# ProProject_AstrAlim_2024-04-22.net
KiCad netlist of a schematic drawn in EasyEDA Pro
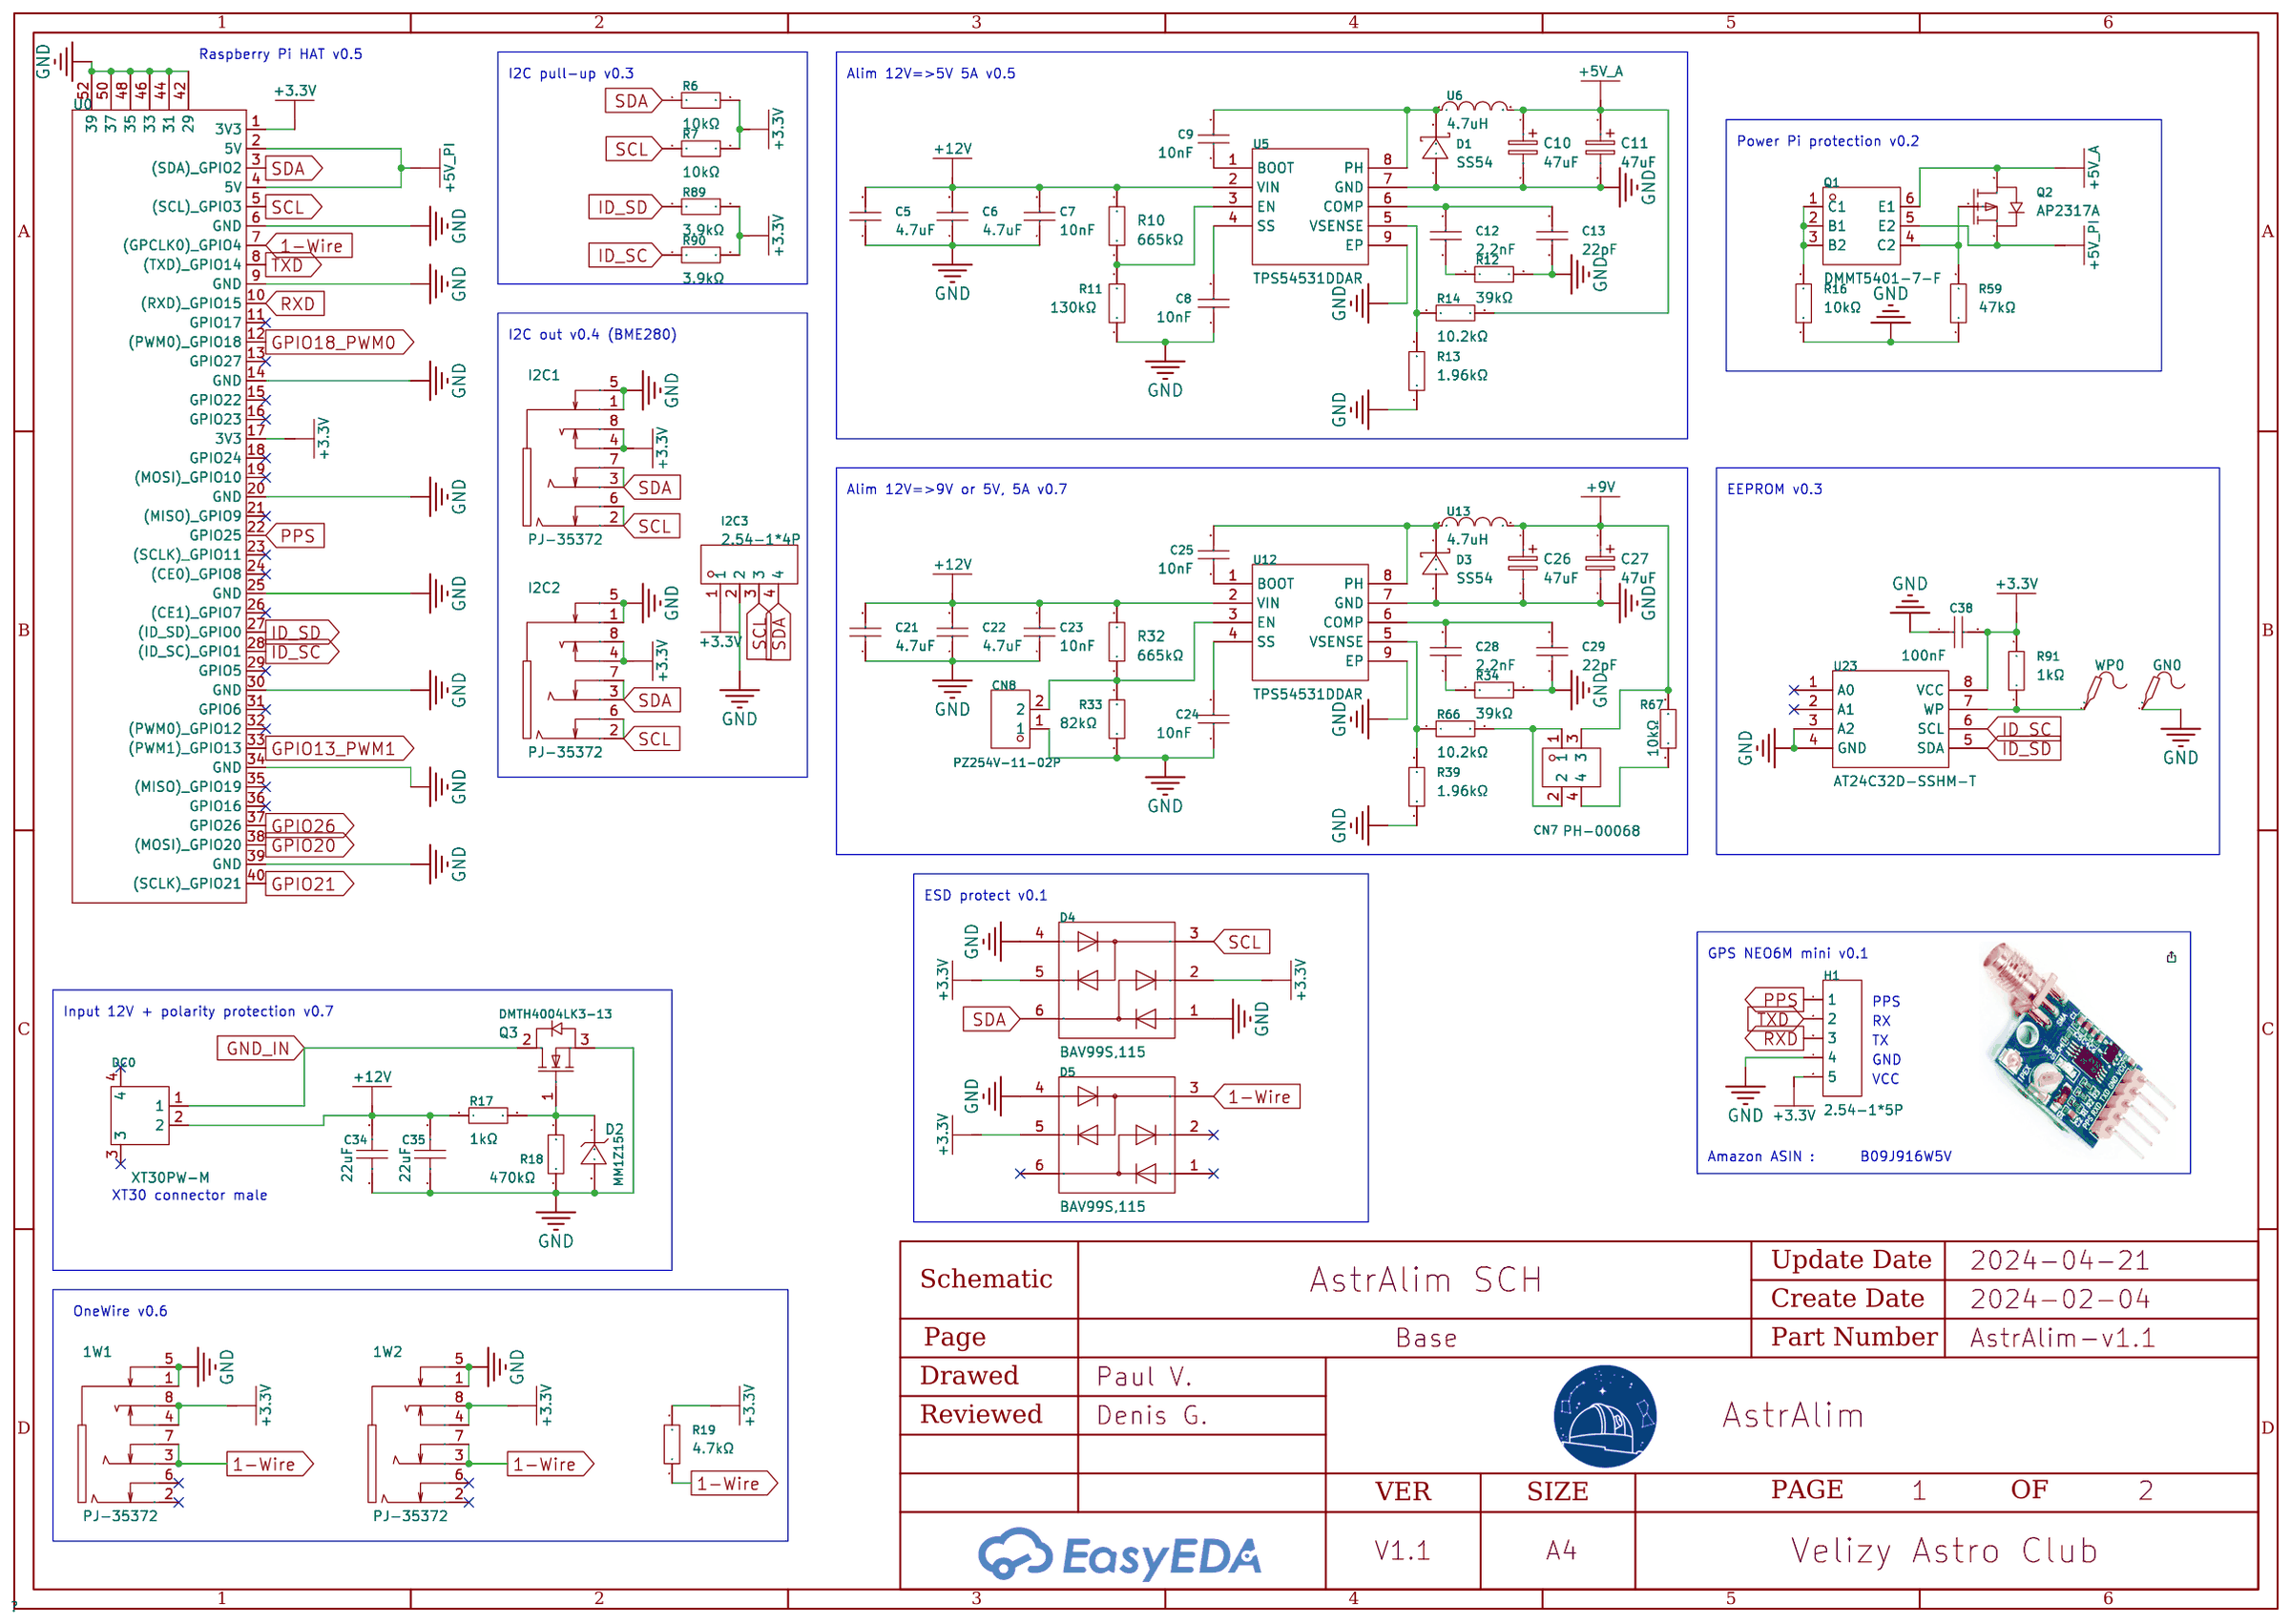
[diagram p0: Base]
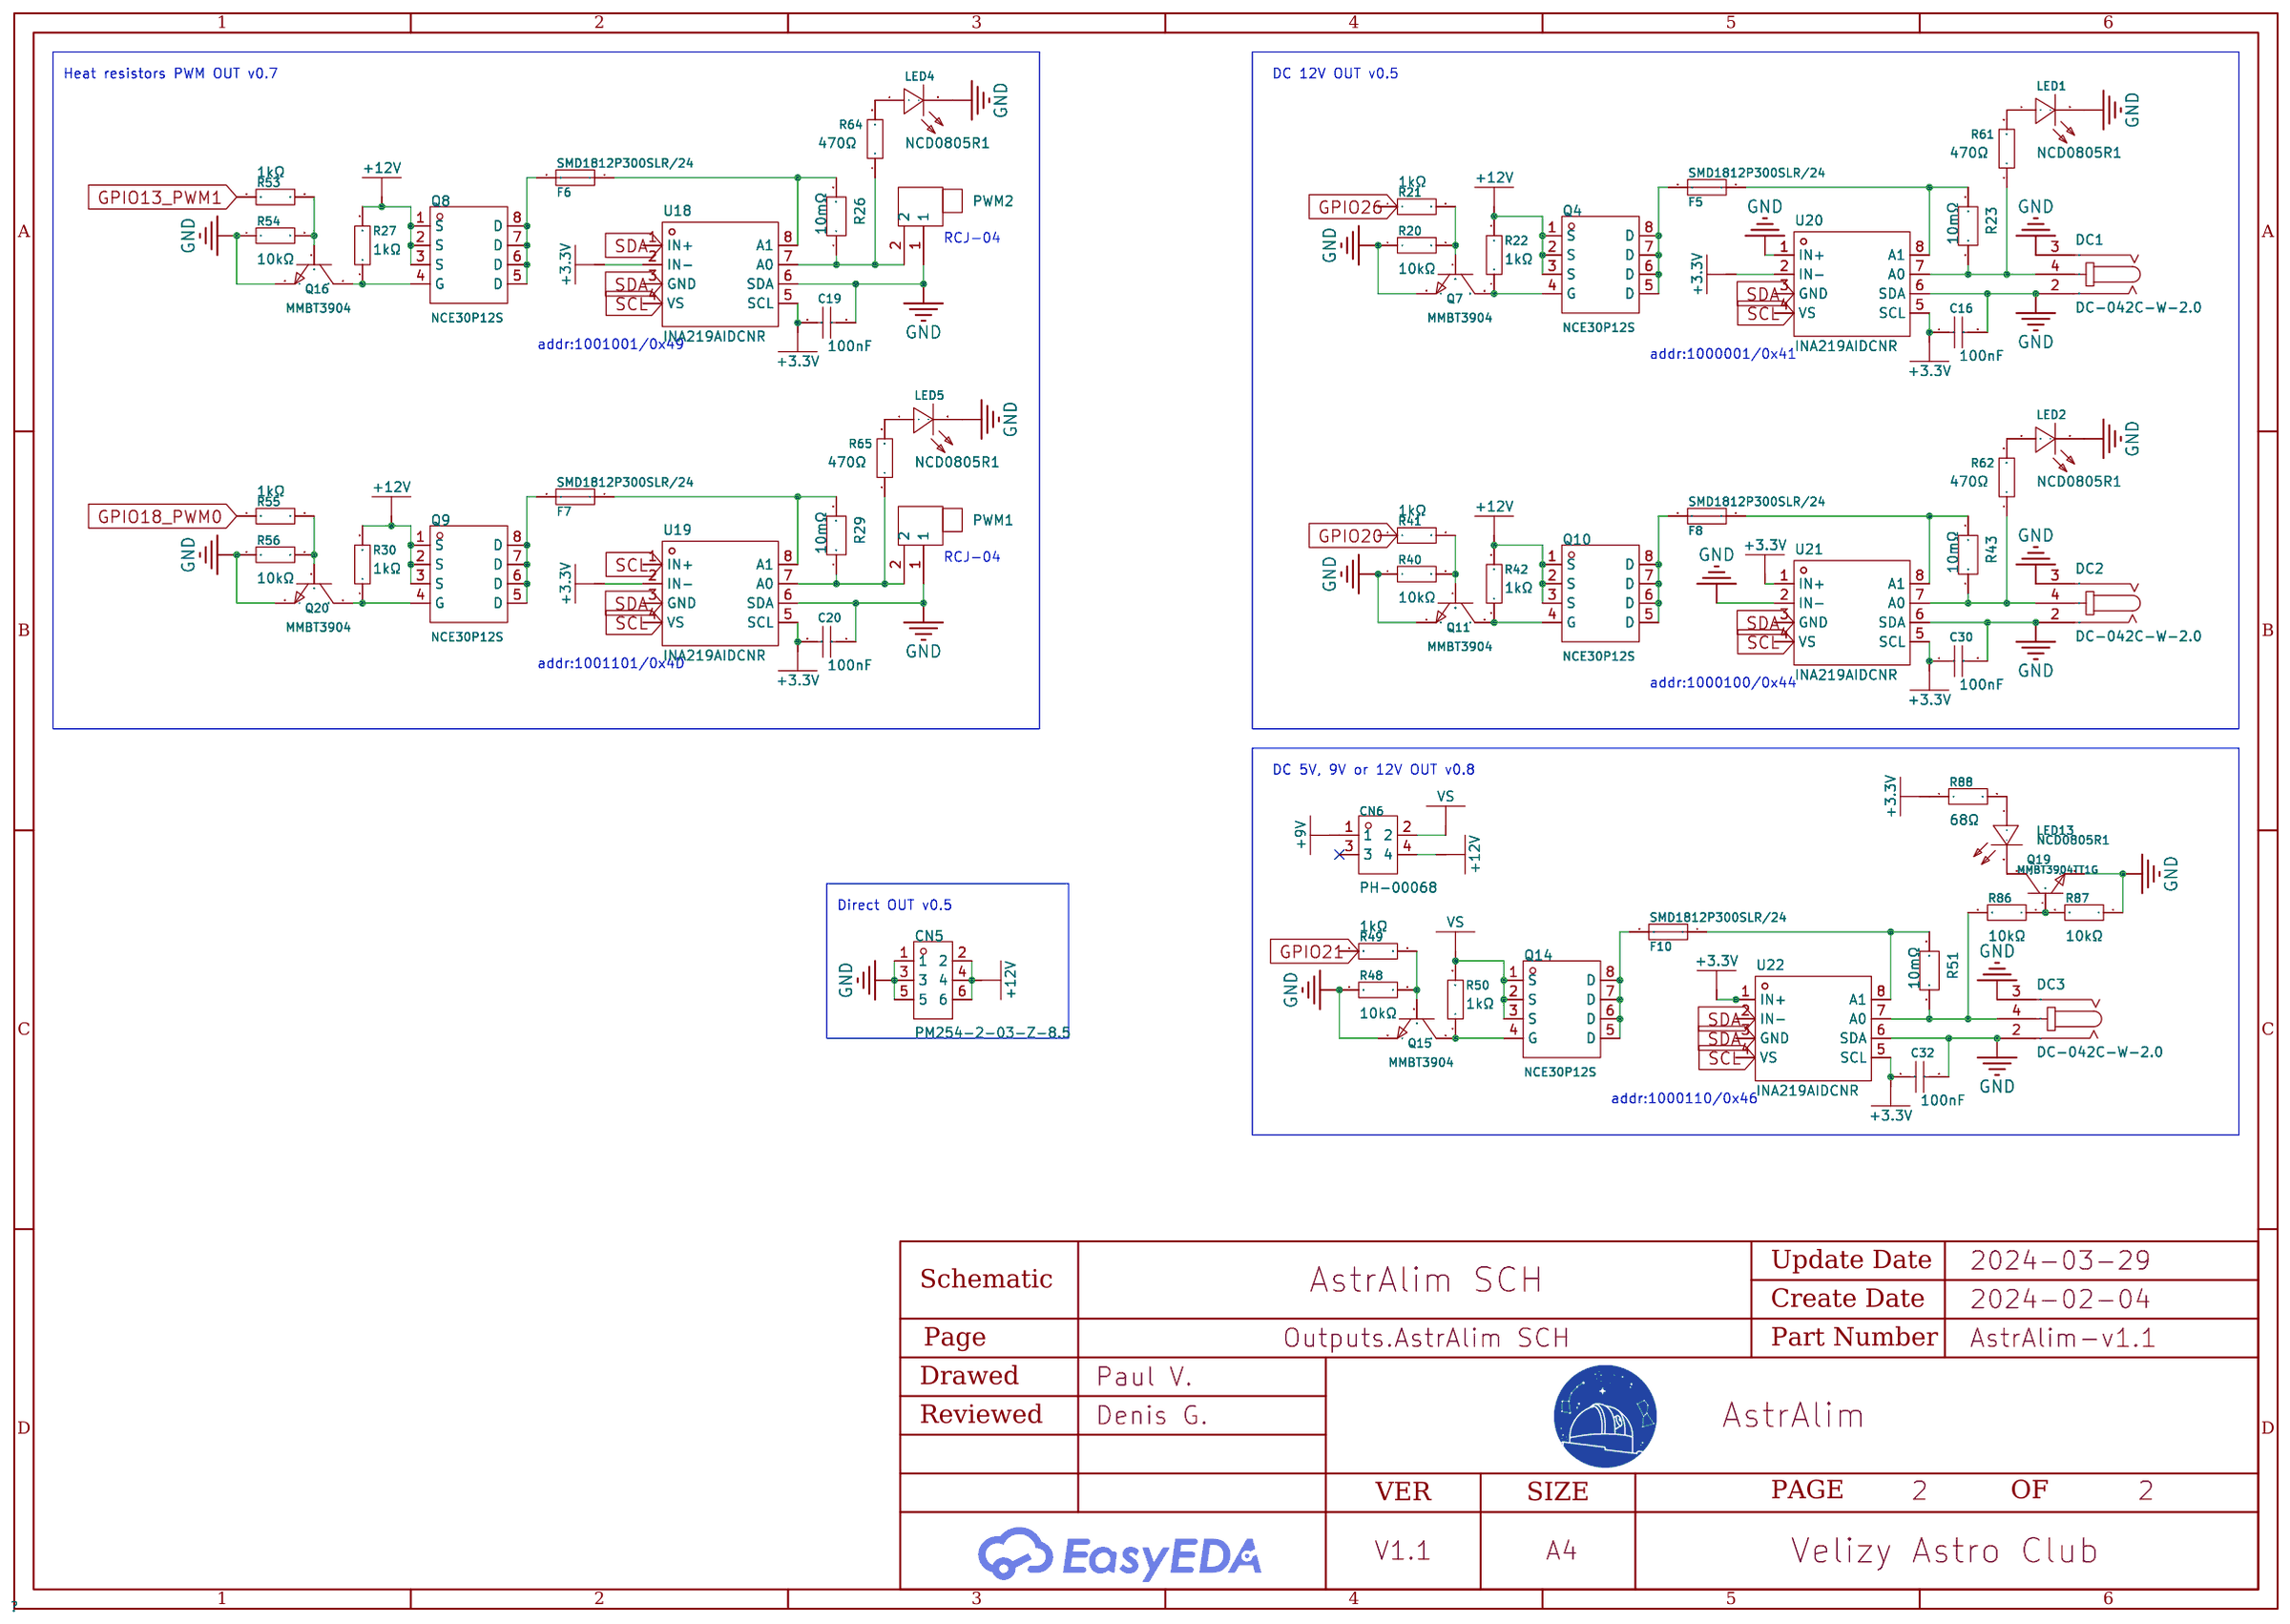
[diagram p1: Outputs]

(export (version "E")
  (design (tool "Eeschema 10.0.6"))
  (components
    (comp (ref "1W1")
      (value "PJ-35372")
      (footprint "easyedapro:AUDIO-TH_PJ-35372")
      (fields (field (name "Manufacturer") "XKB Connectivity(中国星坤)"))
      (libsource (lib "easyedapro") (part "PJ-35372"))
    )
    (comp (ref "1W2")
      (value "PJ-35372")
      (footprint "easyedapro:AUDIO-TH_PJ-35372")
      (fields (field (name "Manufacturer") "XKB Connectivity(中国星坤)"))
      (libsource (lib "easyedapro") (part "PJ-35372"))
    )
    (comp (ref "C5")
      (value "4.7uF")
      (footprint "easyedapro:C0805")
      (fields
        (field (name "Manufacturer Part") "CL21A475KAQNNNE")
        (field (name "Manufacturer") "SAMSUNG(三星)")
      )
      (libsource (lib "easyedapro") (part "CL21A475KAQNNNE"))
    )
    (comp (ref "C6")
      (value "4.7uF")
      (footprint "easyedapro:C0805")
      (fields
        (field (name "Manufacturer Part") "CL21A475KAQNNNE")
        (field (name "Manufacturer") "SAMSUNG(三星)")
      )
      (libsource (lib "easyedapro") (part "CL21A475KAQNNNE"))
    )
    (comp (ref "C7")
      (value "10nF")
      (footprint "easyedapro:C0402")
      (fields
        (field (name "Manufacturer Part") "CL05B103KB5NNNC")
        (field (name "Manufacturer") "SAMSUNG(三星)")
      )
      (libsource (lib "easyedapro") (part "CL05B103KB5NNNC"))
    )
    (comp (ref "C8")
      (value "10nF")
      (footprint "easyedapro:C0402")
      (fields
        (field (name "Manufacturer Part") "CL05B103KB5NNNC")
        (field (name "Manufacturer") "SAMSUNG(三星)")
      )
      (libsource (lib "easyedapro") (part "CL05B103KB5NNNC"))
    )
    (comp (ref "C9")
      (value "10nF")
      (footprint "easyedapro:C0402")
      (fields
        (field (name "Manufacturer Part") "CL05B103KB5NNNC")
        (field (name "Manufacturer") "SAMSUNG(三星)")
      )
      (libsource (lib "easyedapro") (part "CL05B103KB5NNNC"))
    )
    (comp (ref "C10")
      (value "47uF")
      (footprint "easyedapro:CAP-SMD_L3.5-W2.8-R-RD")
      (fields
        (field (name "Manufacturer Part") "CA45-B-16V-47uF-K")
        (field (name "Manufacturer") "CEC(振华新云)")
      )
      (libsource (lib "easyedapro") (part "CA45-B-16V-47UF-K"))
    )
    (comp (ref "C11")
      (value "47uF")
      (footprint "easyedapro:CAP-SMD_L3.5-W2.8-R-RD")
      (fields
        (field (name "Manufacturer Part") "CA45-B-16V-47uF-K")
        (field (name "Manufacturer") "CEC(振华新云)")
      )
      (libsource (lib "easyedapro") (part "CA45-B-16V-47UF-K"))
    )
    (comp (ref "C12")
      (value "2.2nF")
      (footprint "easyedapro:C0603")
      (fields (field (name "Manufacturer Part") "0603B222K500NT") (field (name "Manufacturer") "FH(风华)"))
      (libsource (lib "easyedapro") (part "0603B222K500NT"))
    )
    (comp (ref "C13")
      (value "22pF")
      (footprint "easyedapro:C0402")
      (fields (field (name "Manufacturer Part") "0402CG220J500NT") (field (name "Manufacturer") "FH(风华)"))
      (libsource (lib "easyedapro") (part "0402CG220J500NT"))
    )
    (comp (ref "C21")
      (value "4.7uF")
      (footprint "easyedapro:C0805")
      (fields
        (field (name "Manufacturer Part") "CL21A475KAQNNNE")
        (field (name "Manufacturer") "SAMSUNG(三星)")
      )
      (libsource (lib "easyedapro") (part "CL21A475KAQNNNE"))
    )
    (comp (ref "C22")
      (value "4.7uF")
      (footprint "easyedapro:C0805")
      (fields
        (field (name "Manufacturer Part") "CL21A475KAQNNNE")
        (field (name "Manufacturer") "SAMSUNG(三星)")
      )
      (libsource (lib "easyedapro") (part "CL21A475KAQNNNE"))
    )
    (comp (ref "C23")
      (value "10nF")
      (footprint "easyedapro:C0402")
      (fields
        (field (name "Manufacturer Part") "CL05B103KB5NNNC")
        (field (name "Manufacturer") "SAMSUNG(三星)")
      )
      (libsource (lib "easyedapro") (part "CL05B103KB5NNNC"))
    )
    (comp (ref "C24")
      (value "10nF")
      (footprint "easyedapro:C0402")
      (fields
        (field (name "Manufacturer Part") "CL05B103KB5NNNC")
        (field (name "Manufacturer") "SAMSUNG(三星)")
      )
      (libsource (lib "easyedapro") (part "CL05B103KB5NNNC"))
    )
    (comp (ref "C25")
      (value "10nF")
      (footprint "easyedapro:C0402")
      (fields
        (field (name "Manufacturer Part") "CL05B103KB5NNNC")
        (field (name "Manufacturer") "SAMSUNG(三星)")
      )
      (libsource (lib "easyedapro") (part "CL05B103KB5NNNC"))
    )
    (comp (ref "C26")
      (value "47uF")
      (footprint "easyedapro:CAP-SMD_L3.5-W2.8-R-RD")
      (fields
        (field (name "Manufacturer Part") "CA45-B-16V-47uF-K")
        (field (name "Manufacturer") "CEC(振华新云)")
      )
      (libsource (lib "easyedapro") (part "CA45-B-16V-47UF-K"))
    )
    (comp (ref "C27")
      (value "47uF")
      (footprint "easyedapro:CAP-SMD_L3.5-W2.8-R-RD")
      (fields
        (field (name "Manufacturer Part") "CA45-B-16V-47uF-K")
        (field (name "Manufacturer") "CEC(振华新云)")
      )
      (libsource (lib "easyedapro") (part "CA45-B-16V-47UF-K"))
    )
    (comp (ref "C28")
      (value "2.2nF")
      (footprint "easyedapro:C0603")
      (fields (field (name "Manufacturer Part") "0603B222K500NT") (field (name "Manufacturer") "FH(风华)"))
      (libsource (lib "easyedapro") (part "0603B222K500NT"))
    )
    (comp (ref "C29")
      (value "22pF")
      (footprint "easyedapro:C0402")
      (fields (field (name "Manufacturer Part") "0402CG220J500NT") (field (name "Manufacturer") "FH(风华)"))
      (libsource (lib "easyedapro") (part "0402CG220J500NT"))
    )
    (comp (ref "C34")
      (value "22uF")
      (footprint "easyedapro:C0805")
      (fields
        (field (name "Manufacturer Part") "CL21A226MAQNNNE")
        (field (name "Manufacturer") "SAMSUNG(三星)")
      )
      (libsource (lib "easyedapro") (part "CL21A226MAQNNNE"))
    )
    (comp (ref "C35")
      (value "22uF")
      (footprint "easyedapro:C0805")
      (fields
        (field (name "Manufacturer Part") "CL21A226MAQNNNE")
        (field (name "Manufacturer") "SAMSUNG(三星)")
      )
      (libsource (lib "easyedapro") (part "CL21A226MAQNNNE"))
    )
    (comp (ref "C38")
      (value "100nF")
      (footprint "easyedapro:C0402")
      (fields
        (field (name "Manufacturer Part") "CL05B104KO5NNNC")
        (field (name "Manufacturer") "SAMSUNG(三星)")
      )
      (libsource (lib "easyedapro") (part "CL05B104KO5NNNC"))
    )
    (comp (ref "CN7")
      (value "PH-00068")
      (footprint "easyedapro:HDR-TH_4P-P2.54-V-M-R2-C2-S2.54")
      (fields (field (name "Manufacturer") "Liansheng(连盛)"))
      (libsource (lib "easyedapro") (part "PH-00068"))
    )
    (comp (ref "CN8")
      (value "PZ254V-11-02P")
      (footprint "easyedapro:HDR-TH_2P-P2.54-V-M")
      (fields (field (name "Manufacturer") "XFCN(兴飞)"))
      (libsource (lib "easyedapro") (part "PZ254V-11-02P"))
    )
    (comp (ref "D1")
      (value "SS54")
      (footprint "easyedapro:SMA_L4.4-W2.8-LS5.4-R-RD")
      (fields (field (name "Manufacturer") "MDD"))
      (libsource (lib "easyedapro") (part "SS54_C22452"))
    )
    (comp (ref "D2")
      (value "MM1Z15")
      (footprint "easyedapro:SOD-123_L2.7-W1.6-LS3.7-RD")
      (fields (field (name "Manufacturer") "ST(先科)"))
      (libsource (lib "easyedapro") (part "MM1Z15"))
    )
    (comp (ref "D3")
      (value "SS54")
      (footprint "easyedapro:SMA_L4.4-W2.8-LS5.4-R-RD")
      (fields (field (name "Manufacturer") "MDD"))
      (libsource (lib "easyedapro") (part "SS54_C22452"))
    )
    (comp (ref "D4")
      (value "BAV99S,115")
      (footprint "easyedapro:SOT-363_L2.0-W1.3-P0.65-LS2.1-TL")
      (fields (field (name "Manufacturer") "Nexperia(安世)"))
      (libsource (lib "easyedapro") (part "BAV99S,135"))
    )
    (comp (ref "D5")
      (value "BAV99S,115")
      (footprint "easyedapro:SOT-363_L2.0-W1.3-P0.65-LS2.1-TL")
      (fields (field (name "Manufacturer") "Nexperia(安世)"))
      (libsource (lib "easyedapro") (part "BAV99S,135"))
    )
    (comp (ref "DC0")
      (value "XT30PW-M")
      (footprint "easyedapro:CONN-TH_XT30PW-M")
      (fields (field (name "Manufacturer") "AMASS(艾迈斯)"))
      (libsource (lib "easyedapro") (part "XT30PW-M"))
    )
    (comp (ref "GN0")
      (value "~")
      (footprint "easyedapro:Test-Point-0.5mm")
      (description "Test Point 测试点")
      (libsource (lib "easyedapro") (part "Test-Point"))
    )
    (comp (ref "H1")
      (value "2.54-1*5P")
      (footprint "easyedapro:HDR-TH_5P-P2.54-V-F")
      (fields (field (name "Manufacturer") "BOOMELE(博穆精密)"))
      (libsource (lib "easyedapro") (part "Header-Female-2.54_1x5"))
    )
    (comp (ref "I2C1")
      (value "PJ-35372")
      (footprint "easyedapro:AUDIO-TH_PJ-35372")
      (fields (field (name "Manufacturer") "XKB Connectivity(中国星坤)"))
      (libsource (lib "easyedapro") (part "PJ-35372"))
    )
    (comp (ref "I2C2")
      (value "PJ-35372")
      (footprint "easyedapro:AUDIO-TH_PJ-35372")
      (fields (field (name "Manufacturer") "XKB Connectivity(中国星坤)"))
      (libsource (lib "easyedapro") (part "PJ-35372"))
    )
    (comp (ref "I2C3")
      (value "2.54-1*4P")
      (footprint "easyedapro:HDR-TH_4P-P2.54-V-F")
      (fields (field (name "Manufacturer") "BOOMELE(博穆精密)"))
      (libsource (lib "easyedapro") (part "2.54-1*4P母"))
    )
    (comp (ref "Q1")
      (value "DMMT5401-7-F")
      (footprint "easyedapro:SOT-23-6_L2.9-W1.6-P0.95-LS2.8-BR")
      (fields (field (name "Manufacturer") "DIODES(美台)"))
      (libsource (lib "easyedapro") (part "DMMT5401-7-F"))
    )
    (comp (ref "Q2")
      (value "AP2317A")
      (footprint "easyedapro:SOT-23-3_L2.9-W1.6-P1.90-LS2.8-BR")
      (fields (field (name "Manufacturer") "ALLPOWER(铨力)"))
      (libsource (lib "easyedapro") (part "AP2317A"))
    )
    (comp (ref "Q3")
      (value "DMTH4004LK3-13")
      (footprint "easyedapro:TO-252-2_L6.6-W6.1-P4.58-LS9.9-TL")
      (fields (field (name "Manufacturer") "DIODES(美台)"))
      (libsource (lib "easyedapro") (part "DMTH4004LK3-13"))
    )
    (comp (ref "R6")
      (value "10kΩ")
      (footprint "easyedapro:R0402")
      (fields
        (field (name "Manufacturer Part") "0402WGF1002TCE")
        (field (name "Manufacturer") "UNI-ROYAL(厚声)")
      )
      (libsource (lib "easyedapro") (part "0402WGF1002TCE"))
    )
    (comp (ref "R7")
      (value "10kΩ")
      (footprint "easyedapro:R0402")
      (fields
        (field (name "Manufacturer Part") "0402WGF1002TCE")
        (field (name "Manufacturer") "UNI-ROYAL(厚声)")
      )
      (libsource (lib "easyedapro") (part "0402WGF1002TCE"))
    )
    (comp (ref "R10")
      (value "665kΩ")
      (footprint "easyedapro:R0603")
      (fields (field (name "Manufacturer Part") "AC0603FR-07665KL") (field (name "Manufacturer") "YAGEO(国巨)"))
      (libsource (lib "easyedapro") (part "AC0603FR-07665KL"))
    )
    (comp (ref "R11")
      (value "130kΩ")
      (footprint "easyedapro:R0603")
      (fields
        (field (name "Manufacturer Part") "0603WAF1303T5E")
        (field (name "Manufacturer") "UNI-ROYAL(厚声)")
      )
      (libsource (lib "easyedapro") (part "0603WAF1303T5E"))
    )
    (comp (ref "R12")
      (value "39kΩ")
      (footprint "easyedapro:R0603")
      (fields
        (field (name "Manufacturer Part") "0603WAF3902T5E")
        (field (name "Manufacturer") "UNI-ROYAL(厚声)")
      )
      (libsource (lib "easyedapro") (part "0603WAF3902T5E"))
    )
    (comp (ref "R13")
      (value "1.96kΩ")
      (footprint "easyedapro:R0402")
      (fields
        (field (name "Manufacturer Part") "0402WGF1961TCE")
        (field (name "Manufacturer") "UNI-ROYAL(厚声)")
      )
      (libsource (lib "easyedapro") (part "0402WGF1961TCE"))
    )
    (comp (ref "R14")
      (value "10.2kΩ")
      (footprint "easyedapro:R0402")
      (fields
        (field (name "Manufacturer Part") "0402WGF1022TCE")
        (field (name "Manufacturer") "UNI-ROYAL(厚声)")
      )
      (libsource (lib "easyedapro") (part "0402WGF1022TCE"))
    )
    (comp (ref "R16")
      (value "10kΩ")
      (footprint "easyedapro:R0402")
      (fields
        (field (name "Manufacturer Part") "0402WGF1002TCE")
        (field (name "Manufacturer") "UNI-ROYAL(厚声)")
      )
      (libsource (lib "easyedapro") (part "0402WGF1002TCE"))
    )
    (comp (ref "R17")
      (value "1kΩ")
      (footprint "easyedapro:R0402")
      (fields
        (field (name "Manufacturer Part") "0402WGF1001TCE")
        (field (name "Manufacturer") "UNI-ROYAL(厚声)")
      )
      (libsource (lib "easyedapro") (part "0402WGF1001TCE"))
    )
    (comp (ref "R18")
      (value "470kΩ")
      (footprint "easyedapro:R0603")
      (fields
        (field (name "Manufacturer Part") "0603WAF4703T5E")
        (field (name "Manufacturer") "UNI-ROYAL(厚声)")
      )
      (libsource (lib "easyedapro") (part "0603WAF4703T5E"))
    )
    (comp (ref "R19")
      (value "4.7kΩ")
      (footprint "easyedapro:R0402")
      (fields
        (field (name "Manufacturer Part") "0402WGF4701TCE")
        (field (name "Manufacturer") "UNI-ROYAL(厚声)")
      )
      (libsource (lib "easyedapro") (part "0402WGF4701TCE"))
    )
    (comp (ref "R32")
      (value "665kΩ")
      (footprint "easyedapro:R0603")
      (fields (field (name "Manufacturer Part") "AC0603FR-07665KL") (field (name "Manufacturer") "YAGEO(国巨)"))
      (libsource (lib "easyedapro") (part "AC0603FR-07665KL"))
    )
    (comp (ref "R33")
      (value "82kΩ")
      (footprint "easyedapro:R0603")
      (fields
        (field (name "Manufacturer Part") "0603WAF8202T5E")
        (field (name "Manufacturer") "UNI-ROYAL(厚声)")
      )
      (libsource (lib "easyedapro") (part "0603WAF8202T5E"))
    )
    (comp (ref "R34")
      (value "39kΩ")
      (footprint "easyedapro:R0603")
      (fields
        (field (name "Manufacturer Part") "0603WAF3902T5E")
        (field (name "Manufacturer") "UNI-ROYAL(厚声)")
      )
      (libsource (lib "easyedapro") (part "0603WAF3902T5E"))
    )
    (comp (ref "R39")
      (value "1.96kΩ")
      (footprint "easyedapro:R0402")
      (fields
        (field (name "Manufacturer Part") "0402WGF1961TCE")
        (field (name "Manufacturer") "UNI-ROYAL(厚声)")
      )
      (libsource (lib "easyedapro") (part "0402WGF1961TCE"))
    )
    (comp (ref "R59")
      (value "47kΩ")
      (footprint "easyedapro:R0402")
      (fields
        (field (name "Manufacturer Part") "0402WGF4702TCE")
        (field (name "Manufacturer") "UNI-ROYAL(厚声)")
      )
      (libsource (lib "easyedapro") (part "0402WGF4702TCE"))
    )
    (comp (ref "R66")
      (value "10.2kΩ")
      (footprint "easyedapro:R0402")
      (fields
        (field (name "Manufacturer Part") "0402WGF1022TCE")
        (field (name "Manufacturer") "UNI-ROYAL(厚声)")
      )
      (libsource (lib "easyedapro") (part "0402WGF1022TCE"))
    )
    (comp (ref "R67")
      (value "10kΩ")
      (footprint "easyedapro:R0402")
      (fields
        (field (name "Manufacturer Part") "0402WGF1002TCE")
        (field (name "Manufacturer") "UNI-ROYAL(厚声)")
      )
      (libsource (lib "easyedapro") (part "0402WGF1002TCE"))
    )
    (comp (ref "R89")
      (value "3.9kΩ")
      (footprint "easyedapro:R0603")
      (fields
        (field (name "Manufacturer Part") "0603WAF3901T5E")
        (field (name "Manufacturer") "UNI-ROYAL(厚声)")
      )
      (libsource (lib "easyedapro") (part "0603WAF3901T5E"))
    )
    (comp (ref "R90")
      (value "3.9kΩ")
      (footprint "easyedapro:R0603")
      (fields
        (field (name "Manufacturer Part") "0603WAF3901T5E")
        (field (name "Manufacturer") "UNI-ROYAL(厚声)")
      )
      (libsource (lib "easyedapro") (part "0603WAF3901T5E"))
    )
    (comp (ref "R91")
      (value "1kΩ")
      (footprint "easyedapro:R0402")
      (fields
        (field (name "Manufacturer Part") "0402WGF1001TCE")
        (field (name "Manufacturer") "UNI-ROYAL(厚声)")
      )
      (libsource (lib "easyedapro") (part "0402WGF1001TCE"))
    )
    (comp (ref "U0")
      (value "RASPI HAT FULL")
      (fields (field (name "Manufacturer Part") "RaspberryPi 3"))
      (libsource (lib "easyedapro") (part "RASPI HAT FULL - NO OUTLINE"))
    )
    (comp (ref "U5")
      (value "TPS54531DDAR")
      (footprint "easyedapro:SOIC-8_L5.0-W4.0-P1.27-LS6.0-BL-EP2.0")
      (fields (field (name "Manufacturer") "TI(德州仪器)"))
      (libsource (lib "easyedapro") (part "TPS54531DDAR"))
    )
    (comp (ref "U6")
      (value "4.7uH")
      (footprint "easyedapro:IND-SMD_L7.2-W6.6_GPSR07X0")
      (description "Inductance: Tolerance:±20% Tolerance:±20% Rated Current: DC Resistance (DCR):34.5mΩ")
      (fields (field (name "Manufacturer Part") "CYA0630-4.7UH") (field (name "Manufacturer") "SHOU HAN(首韩)"))
      (libsource (lib "easyedapro") (part "CYA0630-4.7UH"))
    )
    (comp (ref "U12")
      (value "TPS54531DDAR")
      (footprint "easyedapro:SOIC-8_L5.0-W4.0-P1.27-LS6.0-BL-EP2.0")
      (fields (field (name "Manufacturer") "TI(德州仪器)"))
      (libsource (lib "easyedapro") (part "TPS54531DDAR"))
    )
    (comp (ref "U13")
      (value "4.7uH")
      (footprint "easyedapro:IND-SMD_L7.2-W6.6_GPSR07X0")
      (description "Inductance: Tolerance:±20% Tolerance:±20% Rated Current: DC Resistance (DCR):34.5mΩ")
      (fields (field (name "Manufacturer Part") "CYA0630-4.7UH") (field (name "Manufacturer") "SHOU HAN(首韩)"))
      (libsource (lib "easyedapro") (part "CYA0630-4.7UH"))
    )
    (comp (ref "U23")
      (value "AT24C32D-SSHM-T")
      (footprint "easyedapro:SOIC-8_L5.0-W4.0-P1.27-LS6.0-BL")
      (fields (field (name "Manufacturer") "MICROCHIP(美国微芯)"))
      (libsource (lib "easyedapro") (part "AT24C32D-SSHM-T"))
    )
    (comp (ref "WP0")
      (value "~")
      (footprint "easyedapro:Test-Point-0.5mm")
      (description "Test Point 测试点")
      (libsource (lib "easyedapro") (part "Test-Point"))
    )
    (comp (ref "C16")
      (value "100nF")
      (footprint "easyedapro:C0402")
      (fields
        (field (name "Manufacturer Part") "CL05B104KO5NNNC")
        (field (name "Manufacturer") "SAMSUNG(三星)")
      )
      (libsource (lib "easyedapro") (part "CL05B104KO5NNNC"))
    )
    (comp (ref "C19")
      (value "100nF")
      (footprint "easyedapro:C0402")
      (fields
        (field (name "Manufacturer Part") "CL05B104KO5NNNC")
        (field (name "Manufacturer") "SAMSUNG(三星)")
      )
      (libsource (lib "easyedapro") (part "CL05B104KO5NNNC"))
    )
    (comp (ref "C20")
      (value "100nF")
      (footprint "easyedapro:C0402")
      (fields
        (field (name "Manufacturer Part") "CL05B104KO5NNNC")
        (field (name "Manufacturer") "SAMSUNG(三星)")
      )
      (libsource (lib "easyedapro") (part "CL05B104KO5NNNC"))
    )
    (comp (ref "C30")
      (value "100nF")
      (footprint "easyedapro:C0402")
      (fields
        (field (name "Manufacturer Part") "CL05B104KO5NNNC")
        (field (name "Manufacturer") "SAMSUNG(三星)")
      )
      (libsource (lib "easyedapro") (part "CL05B104KO5NNNC"))
    )
    (comp (ref "C32")
      (value "100nF")
      (footprint "easyedapro:C0402")
      (fields
        (field (name "Manufacturer Part") "CL05B104KO5NNNC")
        (field (name "Manufacturer") "SAMSUNG(三星)")
      )
      (libsource (lib "easyedapro") (part "CL05B104KO5NNNC"))
    )
    (comp (ref "CN5")
      (value "PM254-2-03-Z-8.5")
      (footprint "easyedapro:HDR-TH_6P-P2.54-V-F-R2-C3-S2.54")
      (fields (field (name "Manufacturer") "HCTL(华灿天禄)"))
      (libsource (lib "easyedapro") (part "PM254-2-03-Z-8.5"))
    )
    (comp (ref "CN6")
      (value "PH-00068")
      (footprint "easyedapro:HDR-TH_4P-P2.54-V-M-R2-C2-S2.54")
      (fields (field (name "Manufacturer") "Liansheng(连盛)"))
      (libsource (lib "easyedapro") (part "PH-00068"))
    )
    (comp (ref "DC1")
      (value "DC-042C-W-2.0")
      (footprint "easyedapro:DC-IN-TH_DC-042C-W-2.0")
      (fields (field (name "Manufacturer") "XKB Connectivity(中国星坤)"))
      (libsource (lib "easyedapro") (part "DC-042C-W-2.0"))
    )
    (comp (ref "DC2")
      (value "DC-042C-W-2.0")
      (footprint "easyedapro:DC-IN-TH_DC-042C-W-2.0")
      (fields (field (name "Manufacturer") "XKB Connectivity(中国星坤)"))
      (libsource (lib "easyedapro") (part "DC-042C-W-2.0"))
    )
    (comp (ref "DC3")
      (value "DC-042C-W-2.0")
      (footprint "easyedapro:DC-IN-TH_DC-042C-W-2.0")
      (fields (field (name "Manufacturer") "XKB Connectivity(中国星坤)"))
      (libsource (lib "easyedapro") (part "DC-042C-W-2.0"))
    )
    (comp (ref "F5")
      (value "SMD1812P300SLR/24")
      (footprint "easyedapro:F1812")
      (fields (field (name "Manufacturer") "PTTC(聚鼎)"))
      (libsource (lib "easyedapro") (part "SMD1812P300SLR/24_C2892380"))
    )
    (comp (ref "F6")
      (value "SMD1812P300SLR/24")
      (footprint "easyedapro:F1812")
      (fields (field (name "Manufacturer") "PTTC(聚鼎)"))
      (libsource (lib "easyedapro") (part "SMD1812P300SLR/24_C2892380"))
    )
    (comp (ref "F7")
      (value "SMD1812P300SLR/24")
      (footprint "easyedapro:F1812")
      (fields (field (name "Manufacturer") "PTTC(聚鼎)"))
      (libsource (lib "easyedapro") (part "SMD1812P300SLR/24_C2892380"))
    )
    (comp (ref "F8")
      (value "SMD1812P300SLR/24")
      (footprint "easyedapro:F1812")
      (fields (field (name "Manufacturer") "PTTC(聚鼎)"))
      (libsource (lib "easyedapro") (part "SMD1812P300SLR/24_C2892380"))
    )
    (comp (ref "F10")
      (value "SMD1812P300SLR/24")
      (footprint "easyedapro:F1812")
      (fields (field (name "Manufacturer") "PTTC(聚鼎)"))
      (libsource (lib "easyedapro") (part "SMD1812P300SLR/24_C2892380"))
    )
    (comp (ref "LED1")
      (value "NCD0805R1")
      (footprint "easyedapro:LED0805-R-RD")
      (fields (field (name "Manufacturer") "国星光电"))
      (libsource (lib "easyedapro") (part "FC-2012HRK-620D"))
    )
    (comp (ref "LED2")
      (value "NCD0805R1")
      (footprint "easyedapro:LED0805-R-RD")
      (fields (field (name "Manufacturer") "国星光电"))
      (libsource (lib "easyedapro") (part "FC-2012HRK-620D"))
    )
    (comp (ref "LED4")
      (value "NCD0805R1")
      (footprint "easyedapro:LED0805-R-RD")
      (fields (field (name "Manufacturer") "国星光电"))
      (libsource (lib "easyedapro") (part "FC-2012HRK-620D"))
    )
    (comp (ref "LED5")
      (value "NCD0805R1")
      (footprint "easyedapro:LED0805-R-RD")
      (fields (field (name "Manufacturer") "国星光电"))
      (libsource (lib "easyedapro") (part "FC-2012HRK-620D"))
    )
    (comp (ref "LED13")
      (value "NCD0805R1")
      (footprint "easyedapro:LED0805-R-RD")
      (fields (field (name "Manufacturer") "国星光电"))
      (libsource (lib "easyedapro") (part "FC-2012HRK-620D"))
    )
    (comp (ref "PWM1")
      (value "AV-5")
      (footprint "easyedapro:RCJ-04")
      (fields (field (name "Manufacturer") "BOOMELE(博穆精密)"))
      (libsource (lib "easyedapro") (part "AV-5"))
    )
    (comp (ref "PWM2")
      (value "AV-5")
      (footprint "easyedapro:RCJ-04")
      (fields (field (name "Manufacturer") "BOOMELE(博穆精密)"))
      (libsource (lib "easyedapro") (part "AV-5"))
    )
    (comp (ref "Q4")
      (value "NCE30P12S")
      (footprint "easyedapro:SOIC-8_L4.9-W3.9-P1.27-LS6.0-BL")
      (fields (field (name "Manufacturer") "NCE(无锡新洁能)"))
      (libsource (lib "easyedapro") (part "NCE30P12S"))
    )
    (comp (ref "Q7")
      (value "MMBT3904")
      (footprint "easyedapro:SOT-23-3_L2.9-W1.3-P1.90-LS2.4-BR")
      (fields (field (name "Manufacturer") "CJ(江苏长电/长晶)"))
      (libsource (lib "easyedapro") (part "MMBT3904"))
    )
    (comp (ref "Q8")
      (value "NCE30P12S")
      (footprint "easyedapro:SOIC-8_L4.9-W3.9-P1.27-LS6.0-BL")
      (fields (field (name "Manufacturer") "NCE(无锡新洁能)"))
      (libsource (lib "easyedapro") (part "NCE30P12S"))
    )
    (comp (ref "Q9")
      (value "NCE30P12S")
      (footprint "easyedapro:SOIC-8_L4.9-W3.9-P1.27-LS6.0-BL")
      (fields (field (name "Manufacturer") "NCE(无锡新洁能)"))
      (libsource (lib "easyedapro") (part "NCE30P12S"))
    )
    (comp (ref "Q10")
      (value "NCE30P12S")
      (footprint "easyedapro:SOIC-8_L4.9-W3.9-P1.27-LS6.0-BL")
      (fields (field (name "Manufacturer") "NCE(无锡新洁能)"))
      (libsource (lib "easyedapro") (part "NCE30P12S"))
    )
    (comp (ref "Q11")
      (value "MMBT3904")
      (footprint "easyedapro:SOT-23-3_L2.9-W1.3-P1.90-LS2.4-BR")
      (fields (field (name "Manufacturer") "CJ(江苏长电/长晶)"))
      (libsource (lib "easyedapro") (part "MMBT3904"))
    )
    (comp (ref "Q14")
      (value "NCE30P12S")
      (footprint "easyedapro:SOIC-8_L4.9-W3.9-P1.27-LS6.0-BL")
      (fields (field (name "Manufacturer") "NCE(无锡新洁能)"))
      (libsource (lib "easyedapro") (part "NCE30P12S"))
    )
    (comp (ref "Q15")
      (value "MMBT3904")
      (footprint "easyedapro:SOT-23-3_L2.9-W1.3-P1.90-LS2.4-BR")
      (fields (field (name "Manufacturer") "CJ(江苏长电/长晶)"))
      (libsource (lib "easyedapro") (part "MMBT3904"))
    )
    (comp (ref "Q16")
      (value "MMBT3904")
      (footprint "easyedapro:SOT-23-3_L2.9-W1.3-P1.90-LS2.4-BR")
      (fields (field (name "Manufacturer") "CJ(江苏长电/长晶)"))
      (libsource (lib "easyedapro") (part "MMBT3904"))
    )
    (comp (ref "Q19")
      (value "MMBT3904TT1G")
      (footprint "easyedapro:SC-75-3_L1.6-W0.8-P1.00-LS1.6-BR")
      (fields (field (name "Manufacturer") "onsemi(安森美)"))
      (libsource (lib "easyedapro") (part "MMBT3904TT1G"))
    )
    (comp (ref "Q20")
      (value "MMBT3904")
      (footprint "easyedapro:SOT-23-3_L2.9-W1.3-P1.90-LS2.4-BR")
      (fields (field (name "Manufacturer") "CJ(江苏长电/长晶)"))
      (libsource (lib "easyedapro") (part "MMBT3904"))
    )
    (comp (ref "R20")
      (value "10kΩ")
      (footprint "easyedapro:R0402")
      (fields
        (field (name "Manufacturer Part") "0402WGF1002TCE")
        (field (name "Manufacturer") "UNI-ROYAL(厚声)")
      )
      (libsource (lib "easyedapro") (part "0402WGF1002TCE"))
    )
    (comp (ref "R21")
      (value "1kΩ")
      (footprint "easyedapro:R0402")
      (fields
        (field (name "Manufacturer Part") "0402WGF1001TCE")
        (field (name "Manufacturer") "UNI-ROYAL(厚声)")
      )
      (libsource (lib "easyedapro") (part "0402WGF1001TCE"))
    )
    (comp (ref "R22")
      (value "1kΩ")
      (footprint "easyedapro:R0402")
      (fields
        (field (name "Manufacturer Part") "0402WGF1001TCE")
        (field (name "Manufacturer") "UNI-ROYAL(厚声)")
      )
      (libsource (lib "easyedapro") (part "0402WGF1001TCE"))
    )
    (comp (ref "R23")
      (value "10mΩ")
      (footprint "easyedapro:R1206")
      (fields (field (name "Manufacturer Part") "MFJ06HR010FT") (field (name "Manufacturer") "FH(风华)"))
      (libsource (lib "easyedapro") (part "MFJ06HR010FT"))
    )
    (comp (ref "R26")
      (value "10mΩ")
      (footprint "easyedapro:R1206")
      (fields (field (name "Manufacturer Part") "MFJ06HR010FT") (field (name "Manufacturer") "FH(风华)"))
      (libsource (lib "easyedapro") (part "MFJ06HR010FT"))
    )
    (comp (ref "R27")
      (value "1kΩ")
      (footprint "easyedapro:R0402")
      (fields
        (field (name "Manufacturer Part") "0402WGF1001TCE")
        (field (name "Manufacturer") "UNI-ROYAL(厚声)")
      )
      (libsource (lib "easyedapro") (part "0402WGF1001TCE"))
    )
    (comp (ref "R29")
      (value "10mΩ")
      (footprint "easyedapro:R1206")
      (fields (field (name "Manufacturer Part") "MFJ06HR010FT") (field (name "Manufacturer") "FH(风华)"))
      (libsource (lib "easyedapro") (part "MFJ06HR010FT"))
    )
    (comp (ref "R30")
      (value "1kΩ")
      (footprint "easyedapro:R0402")
      (fields
        (field (name "Manufacturer Part") "0402WGF1001TCE")
        (field (name "Manufacturer") "UNI-ROYAL(厚声)")
      )
      (libsource (lib "easyedapro") (part "0402WGF1001TCE"))
    )
    (comp (ref "R40")
      (value "10kΩ")
      (footprint "easyedapro:R0402")
      (fields
        (field (name "Manufacturer Part") "0402WGF1002TCE")
        (field (name "Manufacturer") "UNI-ROYAL(厚声)")
      )
      (libsource (lib "easyedapro") (part "0402WGF1002TCE"))
    )
    (comp (ref "R41")
      (value "1kΩ")
      (footprint "easyedapro:R0402")
      (fields
        (field (name "Manufacturer Part") "0402WGF1001TCE")
        (field (name "Manufacturer") "UNI-ROYAL(厚声)")
      )
      (libsource (lib "easyedapro") (part "0402WGF1001TCE"))
    )
    (comp (ref "R42")
      (value "1kΩ")
      (footprint "easyedapro:R0402")
      (fields
        (field (name "Manufacturer Part") "0402WGF1001TCE")
        (field (name "Manufacturer") "UNI-ROYAL(厚声)")
      )
      (libsource (lib "easyedapro") (part "0402WGF1001TCE"))
    )
    (comp (ref "R43")
      (value "10mΩ")
      (footprint "easyedapro:R1206")
      (fields (field (name "Manufacturer Part") "MFJ06HR010FT") (field (name "Manufacturer") "FH(风华)"))
      (libsource (lib "easyedapro") (part "MFJ06HR010FT"))
    )
    (comp (ref "R48")
      (value "10kΩ")
      (footprint "easyedapro:R0402")
      (fields
        (field (name "Manufacturer Part") "0402WGF1002TCE")
        (field (name "Manufacturer") "UNI-ROYAL(厚声)")
      )
      (libsource (lib "easyedapro") (part "0402WGF1002TCE"))
    )
    (comp (ref "R49")
      (value "1kΩ")
      (footprint "easyedapro:R0402")
      (fields
        (field (name "Manufacturer Part") "0402WGF1001TCE")
        (field (name "Manufacturer") "UNI-ROYAL(厚声)")
      )
      (libsource (lib "easyedapro") (part "0402WGF1001TCE"))
    )
    (comp (ref "R50")
      (value "1kΩ")
      (footprint "easyedapro:R0402")
      (fields
        (field (name "Manufacturer Part") "0402WGF1001TCE")
        (field (name "Manufacturer") "UNI-ROYAL(厚声)")
      )
      (libsource (lib "easyedapro") (part "0402WGF1001TCE"))
    )
    (comp (ref "R51")
      (value "10mΩ")
      (footprint "easyedapro:R1206")
      (fields (field (name "Manufacturer Part") "MFJ06HR010FT") (field (name "Manufacturer") "FH(风华)"))
      (libsource (lib "easyedapro") (part "MFJ06HR010FT"))
    )
    (comp (ref "R53")
      (value "1kΩ")
      (footprint "easyedapro:R0402")
      (fields
        (field (name "Manufacturer Part") "0402WGF1001TCE")
        (field (name "Manufacturer") "UNI-ROYAL(厚声)")
      )
      (libsource (lib "easyedapro") (part "0402WGF1001TCE"))
    )
    (comp (ref "R54")
      (value "10kΩ")
      (footprint "easyedapro:R0402")
      (fields
        (field (name "Manufacturer Part") "0402WGF1002TCE")
        (field (name "Manufacturer") "UNI-ROYAL(厚声)")
      )
      (libsource (lib "easyedapro") (part "0402WGF1002TCE"))
    )
    (comp (ref "R55")
      (value "1kΩ")
      (footprint "easyedapro:R0402")
      (fields
        (field (name "Manufacturer Part") "0402WGF1001TCE")
        (field (name "Manufacturer") "UNI-ROYAL(厚声)")
      )
      (libsource (lib "easyedapro") (part "0402WGF1001TCE"))
    )
    (comp (ref "R56")
      (value "10kΩ")
      (footprint "easyedapro:R0402")
      (fields
        (field (name "Manufacturer Part") "0402WGF1002TCE")
        (field (name "Manufacturer") "UNI-ROYAL(厚声)")
      )
      (libsource (lib "easyedapro") (part "0402WGF1002TCE"))
    )
    (comp (ref "R61")
      (value "470Ω")
      (footprint "easyedapro:R0402")
      (fields
        (field (name "Manufacturer Part") "0402WGF4700TCE")
        (field (name "Manufacturer") "UNI-ROYAL(厚声)")
      )
      (libsource (lib "easyedapro") (part "0402WGF4700TCE"))
    )
    (comp (ref "R62")
      (value "470Ω")
      (footprint "easyedapro:R0402")
      (fields
        (field (name "Manufacturer Part") "0402WGF4700TCE")
        (field (name "Manufacturer") "UNI-ROYAL(厚声)")
      )
      (libsource (lib "easyedapro") (part "0402WGF4700TCE"))
    )
    (comp (ref "R64")
      (value "470Ω")
      (footprint "easyedapro:R0402")
      (fields
        (field (name "Manufacturer Part") "0402WGF4700TCE")
        (field (name "Manufacturer") "UNI-ROYAL(厚声)")
      )
      (libsource (lib "easyedapro") (part "0402WGF4700TCE"))
    )
    (comp (ref "R65")
      (value "470Ω")
      (footprint "easyedapro:R0402")
      (fields
        (field (name "Manufacturer Part") "0402WGF4700TCE")
        (field (name "Manufacturer") "UNI-ROYAL(厚声)")
      )
      (libsource (lib "easyedapro") (part "0402WGF4700TCE"))
    )
    (comp (ref "R86")
      (value "10kΩ")
      (footprint "easyedapro:R0402")
      (fields
        (field (name "Manufacturer Part") "0402WGF1002TCE")
        (field (name "Manufacturer") "UNI-ROYAL(厚声)")
      )
      (libsource (lib "easyedapro") (part "0402WGF1002TCE"))
    )
    (comp (ref "R87")
      (value "10kΩ")
      (footprint "easyedapro:R0402")
      (fields
        (field (name "Manufacturer Part") "0402WGF1002TCE")
        (field (name "Manufacturer") "UNI-ROYAL(厚声)")
      )
      (libsource (lib "easyedapro") (part "0402WGF1002TCE"))
    )
    (comp (ref "R88")
      (value "68Ω")
      (footprint "easyedapro:R0603")
      (fields
        (field (name "Manufacturer Part") "0603WAF680JT5E")
        (field (name "Manufacturer") "UNI-ROYAL(厚声)")
      )
      (libsource (lib "easyedapro") (part "0603WAF680JT5E"))
    )
    (comp (ref "U18")
      (value "INA219AIDCNR")
      (footprint "easyedapro:SOT-23-8_L3.0-W1.7-P0.65-LS2.8-BR")
      (fields (field (name "Manufacturer") "TI(德州仪器)"))
      (libsource (lib "easyedapro") (part "INA219AIDCNR"))
    )
    (comp (ref "U19")
      (value "INA219AIDCNR")
      (footprint "easyedapro:SOT-23-8_L3.0-W1.7-P0.65-LS2.8-BR")
      (fields (field (name "Manufacturer") "TI(德州仪器)"))
      (libsource (lib "easyedapro") (part "INA219AIDCNR"))
    )
    (comp (ref "U20")
      (value "INA219AIDCNR")
      (footprint "easyedapro:SOT-23-8_L3.0-W1.7-P0.65-LS2.8-BR")
      (fields (field (name "Manufacturer") "TI(德州仪器)"))
      (libsource (lib "easyedapro") (part "INA219AIDCNR"))
    )
    (comp (ref "U21")
      (value "INA219AIDCNR")
      (footprint "easyedapro:SOT-23-8_L3.0-W1.7-P0.65-LS2.8-BR")
      (fields (field (name "Manufacturer") "TI(德州仪器)"))
      (libsource (lib "easyedapro") (part "INA219AIDCNR"))
    )
    (comp (ref "U22")
      (value "INA219AIDCNR")
      (footprint "easyedapro:SOT-23-8_L3.0-W1.7-P0.65-LS2.8-BR")
      (fields (field (name "Manufacturer") "TI(德州仪器)"))
      (libsource (lib "easyedapro") (part "INA219AIDCNR"))
    )
  )
  (nets
    (net (code "1") (name "+3.3V") (class "Default")
      (node (ref "1W1") (pin "4") (pinfunction "4_4") (pintype "input"))
      (node (ref "1W1") (pin "8") (pinfunction "8_8") (pintype "input"))
      (node (ref "1W2") (pin "4") (pinfunction "4_4") (pintype "input"))
      (node (ref "1W2") (pin "8") (pinfunction "8_8") (pintype "input"))
      (node (ref "C16") (pin "1") (pinfunction "1_1") (pintype "input"))
      (node (ref "C19") (pin "1") (pinfunction "1_1") (pintype "input"))
      (node (ref "C20") (pin "1") (pinfunction "1_1") (pintype "input"))
      (node (ref "C30") (pin "1") (pinfunction "1_1") (pintype "input"))
      (node (ref "C32") (pin "1") (pinfunction "1_1") (pintype "input"))
      (node (ref "C38") (pin "2") (pinfunction "2_2") (pintype "input"))
      (node (ref "D4") (pin "2") (pinfunction "C_2") (pintype "input"))
      (node (ref "D4") (pin "5") (pinfunction "C_5") (pintype "input"))
      (node (ref "D5") (pin "5") (pinfunction "C_5") (pintype "input"))
      (node (ref "H1") (pin "5") (pinfunction "5_5") (pintype "input"))
      (node (ref "I2C1") (pin "4") (pinfunction "4_4") (pintype "input"))
      (node (ref "I2C1") (pin "8") (pinfunction "8_8") (pintype "input"))
      (node (ref "I2C2") (pin "4") (pinfunction "4_4") (pintype "input"))
      (node (ref "I2C2") (pin "8") (pinfunction "8_8") (pintype "input"))
      (node (ref "I2C3") (pin "1") (pinfunction "1_1") (pintype "input"))
      (node (ref "R19") (pin "2") (pinfunction "2_2") (pintype "input"))
      (node (ref "R6") (pin "2") (pinfunction "2_2") (pintype "input"))
      (node (ref "R7") (pin "2") (pinfunction "2_2") (pintype "input"))
      (node (ref "R88") (pin "1") (pinfunction "1_1") (pintype "input"))
      (node (ref "R89") (pin "2") (pinfunction "2_2") (pintype "input"))
      (node (ref "R90") (pin "2") (pinfunction "2_2") (pintype "input"))
      (node (ref "R91") (pin "2") (pinfunction "2_2") (pintype "input"))
      (node (ref "U0") (pin "1") (pinfunction "3V3_1") (pintype "unspecified"))
      (node (ref "U0") (pin "17") (pinfunction "3V3_17") (pintype "unspecified"))
      (node (ref "U18") (pin "2") (pinfunction "IN-_2") (pintype "unspecified"))
      (node (ref "U18") (pin "5") (pinfunction "SCL_5") (pintype "unspecified"))
      (node (ref "U19") (pin "2") (pinfunction "IN-_2") (pintype "unspecified"))
      (node (ref "U19") (pin "5") (pinfunction "SCL_5") (pintype "unspecified"))
      (node (ref "U20") (pin "2") (pinfunction "IN-_2") (pintype "unspecified"))
      (node (ref "U20") (pin "5") (pinfunction "SCL_5") (pintype "unspecified"))
      (node (ref "U21") (pin "1") (pinfunction "IN+_1") (pintype "unspecified"))
      (node (ref "U21") (pin "5") (pinfunction "SCL_5") (pintype "unspecified"))
      (node (ref "U22") (pin "1") (pinfunction "IN+_1") (pintype "unspecified"))
      (node (ref "U22") (pin "5") (pinfunction "SCL_5") (pintype "unspecified"))
      (node (ref "U23") (pin "8") (pinfunction "VCC_8") (pintype "input"))
    )
    (net (code "2") (name "+5V_A") (class "Default")
      (node (ref "C10") (pin "1") (pinfunction "1_1") (pintype "input"))
      (node (ref "C11") (pin "1") (pinfunction "1_1") (pintype "input"))
      (node (ref "Q1") (pin "6") (pinfunction "E1_6") (pintype "input"))
      (node (ref "Q2") (pin "3") (pinfunction "D_3") (pintype "input"))
      (node (ref "R14") (pin "2") (pinfunction "2_2") (pintype "input"))
      (node (ref "U6") (pin "2") (pinfunction "2_2") (pintype "input"))
    )
    (net (code "3") (name "+5V_PI") (class "Default")
      (node (ref "Q1") (pin "5") (pinfunction "E2_5") (pintype "input"))
      (node (ref "Q2") (pin "2") (pinfunction "S_2") (pintype "input"))
      (node (ref "U0") (pin "2") (pinfunction "5V_2") (pintype "unspecified"))
      (node (ref "U0") (pin "4") (pinfunction "5V_4") (pintype "unspecified"))
    )
    (net (code "4") (name "+9V") (class "Default")
      (node (ref "C26") (pin "1") (pinfunction "1_1") (pintype "input"))
      (node (ref "C27") (pin "1") (pinfunction "1_1") (pintype "input"))
      (node (ref "CN6") (pin "1") (pinfunction "1_1") (pintype "input"))
      (node (ref "CN7") (pin "3") (pinfunction "3_3") (pintype "input"))
      (node (ref "R67") (pin "2") (pinfunction "2_2") (pintype "input"))
      (node (ref "U13") (pin "2") (pinfunction "2_2") (pintype "input"))
    )
    (net (code "5") (name "+12V") (class "Default")
      (node (ref "C21") (pin "2") (pinfunction "2_2") (pintype "input"))
      (node (ref "C22") (pin "2") (pinfunction "2_2") (pintype "input"))
      (node (ref "C23") (pin "2") (pinfunction "2_2") (pintype "input"))
      (node (ref "C34") (pin "2") (pinfunction "2_2") (pintype "input"))
      (node (ref "C35") (pin "2") (pinfunction "2_2") (pintype "input"))
      (node (ref "C5") (pin "2") (pinfunction "2_2") (pintype "input"))
      (node (ref "C6") (pin "2") (pinfunction "2_2") (pintype "input"))
      (node (ref "C7") (pin "2") (pinfunction "2_2") (pintype "input"))
      (node (ref "CN5") (pin "2") (pinfunction "2_2") (pintype "unspecified"))
      (node (ref "CN5") (pin "4") (pinfunction "4_4") (pintype "unspecified"))
      (node (ref "CN5") (pin "6") (pinfunction "6_6") (pintype "unspecified"))
      (node (ref "CN6") (pin "4") (pinfunction "4_4") (pintype "input"))
      (node (ref "DC0") (pin "2") (pinfunction "2_2") (pintype "input"))
      (node (ref "Q10") (pin "1") (pinfunction "S_1") (pintype "input"))
      (node (ref "Q10") (pin "2") (pinfunction "S_2") (pintype "input"))
      (node (ref "Q10") (pin "3") (pinfunction "S_3") (pintype "input"))
      (node (ref "Q4") (pin "1") (pinfunction "S_1") (pintype "input"))
      (node (ref "Q4") (pin "2") (pinfunction "S_2") (pintype "input"))
      (node (ref "Q4") (pin "3") (pinfunction "S_3") (pintype "input"))
      (node (ref "Q8") (pin "1") (pinfunction "S_1") (pintype "input"))
      (node (ref "Q8") (pin "2") (pinfunction "S_2") (pintype "input"))
      (node (ref "Q8") (pin "3") (pinfunction "S_3") (pintype "input"))
      (node (ref "Q9") (pin "1") (pinfunction "S_1") (pintype "input"))
      (node (ref "Q9") (pin "2") (pinfunction "S_2") (pintype "input"))
      (node (ref "Q9") (pin "3") (pinfunction "S_3") (pintype "input"))
      (node (ref "R10") (pin "2") (pinfunction "2_2") (pintype "input"))
      (node (ref "R17") (pin "1") (pinfunction "1_1") (pintype "input"))
      (node (ref "R22") (pin "2") (pinfunction "2_2") (pintype "input"))
      (node (ref "R27") (pin "2") (pinfunction "2_2") (pintype "input"))
      (node (ref "R30") (pin "2") (pinfunction "2_2") (pintype "input"))
      (node (ref "R32") (pin "2") (pinfunction "2_2") (pintype "input"))
      (node (ref "R42") (pin "2") (pinfunction "2_2") (pintype "input"))
      (node (ref "U12") (pin "2") (pinfunction "VIN_2") (pintype "input"))
      (node (ref "U5") (pin "2") (pinfunction "VIN_2") (pintype "input"))
    )
    (net (code "6") (name "1-Wire") (class "Default")
      (node (ref "1W1") (pin "3") (pinfunction "3_3") (pintype "input"))
      (node (ref "1W1") (pin "7") (pinfunction "7_7") (pintype "input"))
      (node (ref "1W2") (pin "3") (pinfunction "3_3") (pintype "input"))
      (node (ref "1W2") (pin "7") (pinfunction "7_7") (pintype "input"))
      (node (ref "D5") (pin "3") (pinfunction "AC_3") (pintype "input"))
      (node (ref "R19") (pin "1") (pinfunction "1_1") (pintype "input"))
      (node (ref "U0") (pin "7") (pinfunction "(GPCLK0)_GPIO4_7") (pintype "unspecified"))
    )
    (net (code "7") (name "GND") (class "Default")
      (node (ref "1W1") (pin "1") (pinfunction "1_1") (pintype "input"))
      (node (ref "1W1") (pin "5") (pinfunction "5_5") (pintype "input"))
      (node (ref "1W2") (pin "1") (pinfunction "1_1") (pintype "input"))
      (node (ref "1W2") (pin "5") (pinfunction "5_5") (pintype "input"))
      (node (ref "C10") (pin "2") (pinfunction "2_2") (pintype "input"))
      (node (ref "C11") (pin "2") (pinfunction "2_2") (pintype "input"))
      (node (ref "C13") (pin "1") (pinfunction "1_1") (pintype "input"))
      (node (ref "C16") (pin "2") (pinfunction "2_2") (pintype "input"))
      (node (ref "C19") (pin "2") (pinfunction "2_2") (pintype "input"))
      (node (ref "C20") (pin "2") (pinfunction "2_2") (pintype "input"))
      (node (ref "C21") (pin "1") (pinfunction "1_1") (pintype "input"))
      (node (ref "C22") (pin "1") (pinfunction "1_1") (pintype "input"))
      (node (ref "C23") (pin "1") (pinfunction "1_1") (pintype "input"))
      (node (ref "C24") (pin "1") (pinfunction "1_1") (pintype "input"))
      (node (ref "C26") (pin "2") (pinfunction "2_2") (pintype "input"))
      (node (ref "C27") (pin "2") (pinfunction "2_2") (pintype "input"))
      (node (ref "C29") (pin "1") (pinfunction "1_1") (pintype "input"))
      (node (ref "C30") (pin "2") (pinfunction "2_2") (pintype "input"))
      (node (ref "C32") (pin "2") (pinfunction "2_2") (pintype "input"))
      (node (ref "C34") (pin "1") (pinfunction "1_1") (pintype "input"))
      (node (ref "C35") (pin "1") (pinfunction "1_1") (pintype "input"))
      (node (ref "C38") (pin "1") (pinfunction "1_1") (pintype "input"))
      (node (ref "C5") (pin "1") (pinfunction "1_1") (pintype "input"))
      (node (ref "C6") (pin "1") (pinfunction "1_1") (pintype "input"))
      (node (ref "C7") (pin "1") (pinfunction "1_1") (pintype "input"))
      (node (ref "C8") (pin "1") (pinfunction "1_1") (pintype "input"))
      (node (ref "CN5") (pin "1") (pinfunction "1_1") (pintype "unspecified"))
      (node (ref "CN5") (pin "3") (pinfunction "3_3") (pintype "unspecified"))
      (node (ref "CN5") (pin "5") (pinfunction "5_5") (pintype "unspecified"))
      (node (ref "CN8") (pin "1") (pinfunction "1_1") (pintype "input"))
      (node (ref "D1") (pin "1") (pinfunction "A_1") (pintype "input"))
      (node (ref "D2") (pin "2") (pinfunction "A_2") (pintype "input"))
      (node (ref "D3") (pin "1") (pinfunction "A_1") (pintype "input"))
      (node (ref "D4") (pin "1") (pinfunction "A_1") (pintype "input"))
      (node (ref "D4") (pin "4") (pinfunction "A_4") (pintype "input"))
      (node (ref "D5") (pin "4") (pinfunction "A_4") (pintype "input"))
      (node (ref "DC1") (pin "2") (pinfunction "2_2") (pintype "input"))
      (node (ref "DC1") (pin "3") (pinfunction "3_3") (pintype "input"))
      (node (ref "DC2") (pin "2") (pinfunction "2_2") (pintype "input"))
      (node (ref "DC2") (pin "3") (pinfunction "3_3") (pintype "input"))
      (node (ref "DC3") (pin "2") (pinfunction "2_2") (pintype "input"))
      (node (ref "DC3") (pin "3") (pinfunction "3_3") (pintype "input"))
      (node (ref "GN0") (pin "1") (pinfunction "1_1") (pintype "unspecified"))
      (node (ref "H1") (pin "4") (pinfunction "4_4") (pintype "input"))
      (node (ref "I2C1") (pin "1") (pinfunction "1_1") (pintype "input"))
      (node (ref "I2C1") (pin "5") (pinfunction "5_5") (pintype "input"))
      (node (ref "I2C2") (pin "1") (pinfunction "1_1") (pintype "input"))
      (node (ref "I2C2") (pin "5") (pinfunction "5_5") (pintype "input"))
      (node (ref "I2C3") (pin "2") (pinfunction "2_2") (pintype "input"))
      (node (ref "LED1") (pin "2") (pinfunction "-_2") (pintype "input"))
      (node (ref "LED2") (pin "2") (pinfunction "-_2") (pintype "input"))
      (node (ref "LED4") (pin "2") (pinfunction "-_2") (pintype "input"))
      (node (ref "LED5") (pin "2") (pinfunction "-_2") (pintype "input"))
      (node (ref "PWM1") (pin "1") (pinfunction "1_1") (pintype "input"))
      (node (ref "PWM2") (pin "1") (pinfunction "1_1") (pintype "input"))
      (node (ref "Q11") (pin "2") (pinfunction "E_2") (pintype "input"))
      (node (ref "Q15") (pin "2") (pinfunction "E_2") (pintype "input"))
      (node (ref "Q16") (pin "2") (pinfunction "E_2") (pintype "input"))
      (node (ref "Q19") (pin "2") (pinfunction "E_2") (pintype "input"))
      (node (ref "Q20") (pin "2") (pinfunction "E_2") (pintype "input"))
      (node (ref "Q3") (pin "3") (pinfunction "S_3") (pintype "input"))
      (node (ref "Q7") (pin "2") (pinfunction "E_2") (pintype "input"))
      (node (ref "R11") (pin "1") (pinfunction "1_1") (pintype "input"))
      (node (ref "R12") (pin "2") (pinfunction "2_2") (pintype "input"))
      (node (ref "R13") (pin "1") (pinfunction "1_1") (pintype "input"))
      (node (ref "R16") (pin "1") (pinfunction "1_1") (pintype "input"))
      (node (ref "R18") (pin "1") (pinfunction "1_1") (pintype "input"))
      (node (ref "R20") (pin "1") (pinfunction "1_1") (pintype "input"))
      (node (ref "R33") (pin "1") (pinfunction "1_1") (pintype "input"))
      (node (ref "R34") (pin "2") (pinfunction "2_2") (pintype "input"))
      (node (ref "R39") (pin "1") (pinfunction "1_1") (pintype "input"))
      (node (ref "R40") (pin "1") (pinfunction "1_1") (pintype "input"))
      (node (ref "R48") (pin "1") (pinfunction "1_1") (pintype "input"))
      (node (ref "R54") (pin "1") (pinfunction "1_1") (pintype "input"))
      (node (ref "R56") (pin "1") (pinfunction "1_1") (pintype "input"))
      (node (ref "R59") (pin "1") (pinfunction "1_1") (pintype "input"))
      (node (ref "R87") (pin "1") (pinfunction "1_1") (pintype "input"))
      (node (ref "U0") (pin "14") (pinfunction "GND_14") (pintype "unspecified"))
      (node (ref "U0") (pin "20") (pinfunction "GND_20") (pintype "unspecified"))
      (node (ref "U0") (pin "25") (pinfunction "GND_25") (pintype "unspecified"))
      (node (ref "U0") (pin "30") (pinfunction "GND_30") (pintype "unspecified"))
      (node (ref "U0") (pin "34") (pinfunction "GND_34") (pintype "unspecified"))
      (node (ref "U0") (pin "39") (pinfunction "GND_39") (pintype "unspecified"))
      (node (ref "U0") (pin "42") (pinfunction "29_42") (pintype "input"))
      (node (ref "U0") (pin "44") (pinfunction "31_44") (pintype "input"))
      (node (ref "U0") (pin "46") (pinfunction "33_46") (pintype "input"))
      (node (ref "U0") (pin "48") (pinfunction "35_48") (pintype "input"))
      (node (ref "U0") (pin "50") (pinfunction "37_50") (pintype "input"))
      (node (ref "U0") (pin "52") (pinfunction "39_52") (pintype "input"))
      (node (ref "U0") (pin "6") (pinfunction "GND_6") (pintype "unspecified"))
      (node (ref "U0") (pin "9") (pinfunction "GND_9") (pintype "unspecified"))
      (node (ref "U12") (pin "7") (pinfunction "GND_7") (pintype "input"))
      (node (ref "U12") (pin "9") (pinfunction "EP_9") (pintype "input"))
      (node (ref "U18") (pin "6") (pinfunction "SDA_6") (pintype "unspecified"))
      (node (ref "U19") (pin "6") (pinfunction "SDA_6") (pintype "unspecified"))
      (node (ref "U20") (pin "1") (pinfunction "IN+_1") (pintype "unspecified"))
      (node (ref "U20") (pin "6") (pinfunction "SDA_6") (pintype "unspecified"))
      (node (ref "U21") (pin "2") (pinfunction "IN-_2") (pintype "unspecified"))
      (node (ref "U21") (pin "6") (pinfunction "SDA_6") (pintype "unspecified"))
      (node (ref "U22") (pin "6") (pinfunction "SDA_6") (pintype "unspecified"))
      (node (ref "U23") (pin "3") (pinfunction "A2_3") (pintype "input"))
      (node (ref "U23") (pin "4") (pinfunction "GND_4") (pintype "input"))
      (node (ref "U5") (pin "7") (pinfunction "GND_7") (pintype "input"))
      (node (ref "U5") (pin "9") (pinfunction "EP_9") (pintype "input"))
    )
    (net (code "8") (name "GND_IN") (class "Default")
      (node (ref "DC0") (pin "1") (pinfunction "1_1") (pintype "input"))
      (node (ref "Q3") (pin "2") (pinfunction "D_2") (pintype "input"))
    )
    (net (code "9") (name "GPIO13_PWM1") (class "Default")
      (node (ref "R53") (pin "1") (pinfunction "1_1") (pintype "input"))
      (node (ref "U0") (pin "33") (pinfunction "(PWM1)_GPIO13_33") (pintype "unspecified"))
    )
    (net (code "10") (name "GPIO18_PWM0") (class "Default")
      (node (ref "R55") (pin "1") (pinfunction "1_1") (pintype "input"))
      (node (ref "U0") (pin "12") (pinfunction "(PWM0)_GPIO18_12") (pintype "unspecified"))
    )
    (net (code "11") (name "GPIO20") (class "Default")
      (node (ref "R41") (pin "1") (pinfunction "1_1") (pintype "input"))
      (node (ref "U0") (pin "38") (pinfunction "(MOSI)_GPIO20_38") (pintype "unspecified"))
    )
    (net (code "12") (name "GPIO21") (class "Default")
      (node (ref "R49") (pin "1") (pinfunction "1_1") (pintype "input"))
      (node (ref "U0") (pin "40") (pinfunction "(SCLK)_GPIO21_40") (pintype "unspecified"))
    )
    (net (code "13") (name "GPIO26") (class "Default")
      (node (ref "R21") (pin "1") (pinfunction "1_1") (pintype "input"))
      (node (ref "U0") (pin "37") (pinfunction "GPIO26_37") (pintype "unspecified"))
    )
    (net (code "14") (name "ID_SC") (class "Default")
      (node (ref "R90") (pin "1") (pinfunction "1_1") (pintype "input"))
      (node (ref "U0") (pin "28") (pinfunction "(ID_SC)_GPIO1_28") (pintype "unspecified"))
      (node (ref "U23") (pin "6") (pinfunction "SCL_6") (pintype "input"))
    )
    (net (code "15") (name "ID_SD") (class "Default")
      (node (ref "R89") (pin "1") (pinfunction "1_1") (pintype "input"))
      (node (ref "U0") (pin "27") (pinfunction "(ID_SD)_GPIO0_27") (pintype "unspecified"))
      (node (ref "U23") (pin "5") (pinfunction "SDA_5") (pintype "input"))
    )
    (net (code "16") (name "Net-(C12-Pad1)") (class "Default")
      (node (ref "C12") (pin "1") (pinfunction "1_1") (pintype "input"))
      (node (ref "R12") (pin "1") (pinfunction "1_1") (pintype "input"))
    )
    (net (code "17") (name "Net-(C28-Pad1)") (class "Default")
      (node (ref "C28") (pin "1") (pinfunction "1_1") (pintype "input"))
      (node (ref "R34") (pin "1") (pinfunction "1_1") (pintype "input"))
    )
    (net (code "18") (name "Net-(CN7-Pad1)") (class "Default")
      (node (ref "CN7") (pin "1") (pinfunction "1_1") (pintype "input"))
      (node (ref "CN7") (pin "2") (pinfunction "2_2") (pintype "input"))
      (node (ref "R66") (pin "2") (pinfunction "2_2") (pintype "input"))
    )
    (net (code "19") (name "Net-(CN7-Pad4)") (class "Default")
      (node (ref "CN7") (pin "4") (pinfunction "4_4") (pintype "input"))
      (node (ref "R67") (pin "1") (pinfunction "1_1") (pintype "input"))
    )
    (net (code "20") (name "Net-(D1-K)") (class "Default")
      (node (ref "C9") (pin "2") (pinfunction "2_2") (pintype "input"))
      (node (ref "D1") (pin "2") (pinfunction "K_2") (pintype "input"))
      (node (ref "U5") (pin "8") (pinfunction "PH_8") (pintype "input"))
      (node (ref "U6") (pin "1") (pinfunction "1_1") (pintype "input"))
    )
    (net (code "21") (name "Net-(D2-C)") (class "Default")
      (node (ref "D2") (pin "1") (pinfunction "C_1") (pintype "input"))
      (node (ref "Q3") (pin "1") (pinfunction "G_1") (pintype "input"))
      (node (ref "R17") (pin "2") (pinfunction "2_2") (pintype "input"))
      (node (ref "R18") (pin "2") (pinfunction "2_2") (pintype "input"))
    )
    (net (code "22") (name "Net-(D3-K)") (class "Default")
      (node (ref "C25") (pin "2") (pinfunction "2_2") (pintype "input"))
      (node (ref "D3") (pin "2") (pinfunction "K_2") (pintype "input"))
      (node (ref "U12") (pin "8") (pinfunction "PH_8") (pintype "input"))
      (node (ref "U13") (pin "1") (pinfunction "1_1") (pintype "input"))
    )
    (net (code "23") (name "Net-(F5-Pad2)") (class "Default")
      (node (ref "F5") (pin "2") (pinfunction "2_2") (pintype "input"))
      (node (ref "Q4") (pin "5") (pinfunction "D_5") (pintype "input"))
      (node (ref "Q4") (pin "6") (pinfunction "D_6") (pintype "input"))
      (node (ref "Q4") (pin "7") (pinfunction "D_7") (pintype "input"))
      (node (ref "Q4") (pin "8") (pinfunction "D_8") (pintype "input"))
    )
    (net (code "24") (name "Net-(F6-Pad2)") (class "Default")
      (node (ref "F6") (pin "2") (pinfunction "2_2") (pintype "input"))
      (node (ref "Q8") (pin "5") (pinfunction "D_5") (pintype "input"))
      (node (ref "Q8") (pin "6") (pinfunction "D_6") (pintype "input"))
      (node (ref "Q8") (pin "7") (pinfunction "D_7") (pintype "input"))
      (node (ref "Q8") (pin "8") (pinfunction "D_8") (pintype "input"))
    )
    (net (code "25") (name "Net-(F7-Pad2)") (class "Default")
      (node (ref "F7") (pin "2") (pinfunction "2_2") (pintype "input"))
      (node (ref "Q9") (pin "5") (pinfunction "D_5") (pintype "input"))
      (node (ref "Q9") (pin "6") (pinfunction "D_6") (pintype "input"))
      (node (ref "Q9") (pin "7") (pinfunction "D_7") (pintype "input"))
      (node (ref "Q9") (pin "8") (pinfunction "D_8") (pintype "input"))
    )
    (net (code "26") (name "Net-(F8-Pad2)") (class "Default")
      (node (ref "F8") (pin "2") (pinfunction "2_2") (pintype "input"))
      (node (ref "Q10") (pin "5") (pinfunction "D_5") (pintype "input"))
      (node (ref "Q10") (pin "6") (pinfunction "D_6") (pintype "input"))
      (node (ref "Q10") (pin "7") (pinfunction "D_7") (pintype "input"))
      (node (ref "Q10") (pin "8") (pinfunction "D_8") (pintype "input"))
    )
    (net (code "27") (name "Net-(F10-Pad2)") (class "Default")
      (node (ref "F10") (pin "2") (pinfunction "2_2") (pintype "input"))
      (node (ref "Q14") (pin "5") (pinfunction "D_5") (pintype "input"))
      (node (ref "Q14") (pin "6") (pinfunction "D_6") (pintype "input"))
      (node (ref "Q14") (pin "7") (pinfunction "D_7") (pintype "input"))
      (node (ref "Q14") (pin "8") (pinfunction "D_8") (pintype "input"))
    )
    (net (code "28") (name "Net-(LED1-+)") (class "Default")
      (node (ref "LED1") (pin "1") (pinfunction "+_1") (pintype "input"))
      (node (ref "R61") (pin "2") (pinfunction "2_2") (pintype "input"))
    )
    (net (code "29") (name "Net-(LED2-+)") (class "Default")
      (node (ref "LED2") (pin "1") (pinfunction "+_1") (pintype "input"))
      (node (ref "R62") (pin "2") (pinfunction "2_2") (pintype "input"))
    )
    (net (code "30") (name "Net-(LED4-+)") (class "Default")
      (node (ref "LED4") (pin "1") (pinfunction "+_1") (pintype "input"))
      (node (ref "R64") (pin "2") (pinfunction "2_2") (pintype "input"))
    )
    (net (code "31") (name "Net-(LED5-+)") (class "Default")
      (node (ref "LED5") (pin "1") (pinfunction "+_1") (pintype "input"))
      (node (ref "R65") (pin "2") (pinfunction "2_2") (pintype "input"))
    )
    (net (code "32") (name "Net-(LED13-+)") (class "Default")
      (node (ref "LED13") (pin "1") (pinfunction "+_1") (pintype "input"))
      (node (ref "R88") (pin "2") (pinfunction "2_2") (pintype "input"))
    )
    (net (code "33") (name "Net-(LED13--)") (class "Default")
      (node (ref "LED13") (pin "2") (pinfunction "-_2") (pintype "input"))
      (node (ref "Q19") (pin "3") (pinfunction "C_3") (pintype "input"))
    )
    (net (code "34") (name "Net-(Q1-B1)") (class "Default")
      (node (ref "Q1") (pin "1") (pinfunction "C1_1") (pintype "input"))
      (node (ref "Q1") (pin "2") (pinfunction "B1_2") (pintype "input"))
      (node (ref "Q1") (pin "3") (pinfunction "B2_3") (pintype "input"))
      (node (ref "R16") (pin "2") (pinfunction "2_2") (pintype "input"))
    )
    (net (code "35") (name "Net-(Q1-C2)") (class "Default")
      (node (ref "Q1") (pin "4") (pinfunction "C2_4") (pintype "input"))
      (node (ref "Q2") (pin "1") (pinfunction "G_1") (pintype "input"))
      (node (ref "R59") (pin "2") (pinfunction "2_2") (pintype "input"))
    )
    (net (code "36") (name "Net-(Q4-G)") (class "Default")
      (node (ref "Q4") (pin "4") (pinfunction "G_4") (pintype "input"))
      (node (ref "Q7") (pin "3") (pinfunction "C_3") (pintype "input"))
      (node (ref "R22") (pin "1") (pinfunction "1_1") (pintype "input"))
    )
    (net (code "37") (name "Net-(Q7-B)") (class "Default")
      (node (ref "Q7") (pin "1") (pinfunction "B_1") (pintype "input"))
      (node (ref "R20") (pin "2") (pinfunction "2_2") (pintype "input"))
      (node (ref "R21") (pin "2") (pinfunction "2_2") (pintype "input"))
    )
    (net (code "38") (name "Net-(Q10-G)") (class "Default")
      (node (ref "Q10") (pin "4") (pinfunction "G_4") (pintype "input"))
      (node (ref "Q11") (pin "3") (pinfunction "C_3") (pintype "input"))
      (node (ref "R42") (pin "1") (pinfunction "1_1") (pintype "input"))
    )
    (net (code "39") (name "Net-(Q11-B)") (class "Default")
      (node (ref "Q11") (pin "1") (pinfunction "B_1") (pintype "input"))
      (node (ref "R40") (pin "2") (pinfunction "2_2") (pintype "input"))
      (node (ref "R41") (pin "2") (pinfunction "2_2") (pintype "input"))
    )
    (net (code "40") (name "Net-(Q14-G)") (class "Default")
      (node (ref "Q14") (pin "4") (pinfunction "G_4") (pintype "input"))
      (node (ref "Q15") (pin "3") (pinfunction "C_3") (pintype "input"))
      (node (ref "R50") (pin "1") (pinfunction "1_1") (pintype "input"))
    )
    (net (code "41") (name "Net-(Q15-B)") (class "Default")
      (node (ref "Q15") (pin "1") (pinfunction "B_1") (pintype "input"))
      (node (ref "R48") (pin "2") (pinfunction "2_2") (pintype "input"))
      (node (ref "R49") (pin "2") (pinfunction "2_2") (pintype "input"))
    )
    (net (code "42") (name "Net-(Q16-B)") (class "Default")
      (node (ref "Q16") (pin "1") (pinfunction "B_1") (pintype "input"))
      (node (ref "R53") (pin "2") (pinfunction "2_2") (pintype "input"))
      (node (ref "R54") (pin "2") (pinfunction "2_2") (pintype "input"))
    )
    (net (code "43") (name "Net-(Q16-C)") (class "Default")
      (node (ref "Q16") (pin "3") (pinfunction "C_3") (pintype "input"))
      (node (ref "Q8") (pin "4") (pinfunction "G_4") (pintype "input"))
      (node (ref "R27") (pin "1") (pinfunction "1_1") (pintype "input"))
    )
    (net (code "44") (name "Net-(Q19-B)") (class "Default")
      (node (ref "Q19") (pin "1") (pinfunction "B_1") (pintype "input"))
      (node (ref "R86") (pin "1") (pinfunction "1_1") (pintype "input"))
      (node (ref "R87") (pin "2") (pinfunction "2_2") (pintype "input"))
    )
    (net (code "45") (name "Net-(Q20-B)") (class "Default")
      (node (ref "Q20") (pin "1") (pinfunction "B_1") (pintype "input"))
      (node (ref "R55") (pin "2") (pinfunction "2_2") (pintype "input"))
      (node (ref "R56") (pin "2") (pinfunction "2_2") (pintype "input"))
    )
    (net (code "46") (name "Net-(Q20-C)") (class "Default")
      (node (ref "Q20") (pin "3") (pinfunction "C_3") (pintype "input"))
      (node (ref "Q9") (pin "4") (pinfunction "G_4") (pintype "input"))
      (node (ref "R30") (pin "1") (pinfunction "1_1") (pintype "input"))
    )
    (net (code "47") (name "Net-(U5-BOOT)") (class "Default")
      (node (ref "C9") (pin "1") (pinfunction "1_1") (pintype "input"))
      (node (ref "U5") (pin "1") (pinfunction "BOOT_1") (pintype "input"))
    )
    (net (code "48") (name "Net-(U5-COMP)") (class "Default")
      (node (ref "C12") (pin "2") (pinfunction "2_2") (pintype "input"))
      (node (ref "C13") (pin "2") (pinfunction "2_2") (pintype "input"))
      (node (ref "U5") (pin "6") (pinfunction "COMP_6") (pintype "input"))
    )
    (net (code "49") (name "Net-(U5-EN)") (class "Default")
      (node (ref "R10") (pin "1") (pinfunction "1_1") (pintype "input"))
      (node (ref "R11") (pin "2") (pinfunction "2_2") (pintype "input"))
      (node (ref "U5") (pin "3") (pinfunction "EN_3") (pintype "input"))
    )
    (net (code "50") (name "Net-(U5-SS)") (class "Default")
      (node (ref "C8") (pin "2") (pinfunction "2_2") (pintype "input"))
      (node (ref "U5") (pin "4") (pinfunction "SS_4") (pintype "input"))
    )
    (net (code "51") (name "Net-(U5-VSENSE)") (class "Default")
      (node (ref "R13") (pin "2") (pinfunction "2_2") (pintype "input"))
      (node (ref "R14") (pin "1") (pinfunction "1_1") (pintype "input"))
      (node (ref "U5") (pin "5") (pinfunction "VSENSE_5") (pintype "input"))
    )
    (net (code "52") (name "Net-(U12-BOOT)") (class "Default")
      (node (ref "C25") (pin "1") (pinfunction "1_1") (pintype "input"))
      (node (ref "U12") (pin "1") (pinfunction "BOOT_1") (pintype "input"))
    )
    (net (code "53") (name "Net-(U12-COMP)") (class "Default")
      (node (ref "C28") (pin "2") (pinfunction "2_2") (pintype "input"))
      (node (ref "C29") (pin "2") (pinfunction "2_2") (pintype "input"))
      (node (ref "U12") (pin "6") (pinfunction "COMP_6") (pintype "input"))
    )
    (net (code "54") (name "Net-(U12-EN)") (class "Default")
      (node (ref "CN8") (pin "2") (pinfunction "2_2") (pintype "input"))
      (node (ref "R32") (pin "1") (pinfunction "1_1") (pintype "input"))
      (node (ref "R33") (pin "2") (pinfunction "2_2") (pintype "input"))
      (node (ref "U12") (pin "3") (pinfunction "EN_3") (pintype "input"))
    )
    (net (code "55") (name "Net-(U12-SS)") (class "Default")
      (node (ref "C24") (pin "2") (pinfunction "2_2") (pintype "input"))
      (node (ref "U12") (pin "4") (pinfunction "SS_4") (pintype "input"))
    )
    (net (code "56") (name "Net-(U12-VSENSE)") (class "Default")
      (node (ref "R39") (pin "2") (pinfunction "2_2") (pintype "input"))
      (node (ref "R66") (pin "1") (pinfunction "1_1") (pintype "input"))
      (node (ref "U12") (pin "5") (pinfunction "VSENSE_5") (pintype "input"))
    )
    (net (code "57") (name "Net-(U18-A0)") (class "Default")
      (node (ref "PWM2") (pin "2") (pinfunction "2_2") (pintype "input"))
      (node (ref "R26") (pin "1") (pinfunction "1_1") (pintype "input"))
      (node (ref "R64") (pin "1") (pinfunction "1_1") (pintype "input"))
      (node (ref "U18") (pin "7") (pinfunction "A0_7") (pintype "unspecified"))
    )
    (net (code "58") (name "Net-(U18-A1)") (class "Default")
      (node (ref "F6") (pin "1") (pinfunction "1_1") (pintype "input"))
      (node (ref "R26") (pin "2") (pinfunction "2_2") (pintype "input"))
      (node (ref "U18") (pin "8") (pinfunction "A1_8") (pintype "unspecified"))
    )
    (net (code "59") (name "Net-(U19-A0)") (class "Default")
      (node (ref "PWM1") (pin "2") (pinfunction "2_2") (pintype "input"))
      (node (ref "R29") (pin "1") (pinfunction "1_1") (pintype "input"))
      (node (ref "R65") (pin "1") (pinfunction "1_1") (pintype "input"))
      (node (ref "U19") (pin "7") (pinfunction "A0_7") (pintype "unspecified"))
    )
    (net (code "60") (name "Net-(U19-A1)") (class "Default")
      (node (ref "F7") (pin "1") (pinfunction "1_1") (pintype "input"))
      (node (ref "R29") (pin "2") (pinfunction "2_2") (pintype "input"))
      (node (ref "U19") (pin "8") (pinfunction "A1_8") (pintype "unspecified"))
    )
    (net (code "61") (name "Net-(U20-A0)") (class "Default")
      (node (ref "DC1") (pin "4") (pinfunction "4_4") (pintype "input"))
      (node (ref "R23") (pin "1") (pinfunction "1_1") (pintype "input"))
      (node (ref "R61") (pin "1") (pinfunction "1_1") (pintype "input"))
      (node (ref "U20") (pin "7") (pinfunction "A0_7") (pintype "unspecified"))
    )
    (net (code "62") (name "Net-(U20-A1)") (class "Default")
      (node (ref "F5") (pin "1") (pinfunction "1_1") (pintype "input"))
      (node (ref "R23") (pin "2") (pinfunction "2_2") (pintype "input"))
      (node (ref "U20") (pin "8") (pinfunction "A1_8") (pintype "unspecified"))
    )
    (net (code "63") (name "Net-(U21-A0)") (class "Default")
      (node (ref "DC2") (pin "4") (pinfunction "4_4") (pintype "input"))
      (node (ref "R43") (pin "1") (pinfunction "1_1") (pintype "input"))
      (node (ref "R62") (pin "1") (pinfunction "1_1") (pintype "input"))
      (node (ref "U21") (pin "7") (pinfunction "A0_7") (pintype "unspecified"))
    )
    (net (code "64") (name "Net-(U21-A1)") (class "Default")
      (node (ref "F8") (pin "1") (pinfunction "1_1") (pintype "input"))
      (node (ref "R43") (pin "2") (pinfunction "2_2") (pintype "input"))
      (node (ref "U21") (pin "8") (pinfunction "A1_8") (pintype "unspecified"))
    )
    (net (code "65") (name "Net-(U22-A0)") (class "Default")
      (node (ref "DC3") (pin "4") (pinfunction "4_4") (pintype "input"))
      (node (ref "R51") (pin "1") (pinfunction "1_1") (pintype "input"))
      (node (ref "R86") (pin "2") (pinfunction "2_2") (pintype "input"))
      (node (ref "U22") (pin "7") (pinfunction "A0_7") (pintype "unspecified"))
    )
    (net (code "66") (name "Net-(U22-A1)") (class "Default")
      (node (ref "F10") (pin "1") (pinfunction "1_1") (pintype "input"))
      (node (ref "R51") (pin "2") (pinfunction "2_2") (pintype "input"))
      (node (ref "U22") (pin "8") (pinfunction "A1_8") (pintype "unspecified"))
    )
    (net (code "67") (name "Net-(U23-WP)") (class "Default")
      (node (ref "R91") (pin "1") (pinfunction "1_1") (pintype "input"))
      (node (ref "U23") (pin "7") (pinfunction "WP_7") (pintype "input"))
      (node (ref "WP0") (pin "1") (pinfunction "1_1") (pintype "unspecified"))
    )
    (net (code "68") (name "PPS") (class "Default")
      (node (ref "H1") (pin "1") (pinfunction "1_1") (pintype "input"))
      (node (ref "U0") (pin "22") (pinfunction "GPIO25_22") (pintype "unspecified"))
    )
    (net (code "69") (name "RXD") (class "Default")
      (node (ref "H1") (pin "3") (pinfunction "3_3") (pintype "input"))
      (node (ref "U0") (pin "10") (pinfunction "(RXD)_GPIO15_10") (pintype "unspecified"))
    )
    (net (code "70") (name "SCL") (class "Default")
      (node (ref "D4") (pin "3") (pinfunction "AC_3") (pintype "input"))
      (node (ref "I2C1") (pin "2") (pinfunction "2_2") (pintype "input"))
      (node (ref "I2C1") (pin "6") (pinfunction "6_6") (pintype "input"))
      (node (ref "I2C2") (pin "2") (pinfunction "2_2") (pintype "input"))
      (node (ref "I2C2") (pin "6") (pinfunction "6_6") (pintype "input"))
      (node (ref "I2C3") (pin "3") (pinfunction "3_3") (pintype "input"))
      (node (ref "R7") (pin "1") (pinfunction "1_1") (pintype "input"))
      (node (ref "U0") (pin "5") (pinfunction "(SCL)_GPIO3_5") (pintype "unspecified"))
      (node (ref "U18") (pin "4") (pinfunction "VS_4") (pintype "unspecified"))
      (node (ref "U19") (pin "1") (pinfunction "IN+_1") (pintype "unspecified"))
      (node (ref "U19") (pin "4") (pinfunction "VS_4") (pintype "unspecified"))
      (node (ref "U20") (pin "4") (pinfunction "VS_4") (pintype "unspecified"))
      (node (ref "U21") (pin "4") (pinfunction "VS_4") (pintype "unspecified"))
      (node (ref "U22") (pin "4") (pinfunction "VS_4") (pintype "unspecified"))
    )
    (net (code "71") (name "SDA") (class "Default")
      (node (ref "D4") (pin "6") (pinfunction "AC_6") (pintype "input"))
      (node (ref "I2C1") (pin "3") (pinfunction "3_3") (pintype "input"))
      (node (ref "I2C1") (pin "7") (pinfunction "7_7") (pintype "input"))
      (node (ref "I2C2") (pin "3") (pinfunction "3_3") (pintype "input"))
      (node (ref "I2C2") (pin "7") (pinfunction "7_7") (pintype "input"))
      (node (ref "I2C3") (pin "4") (pinfunction "4_4") (pintype "input"))
      (node (ref "R6") (pin "1") (pinfunction "1_1") (pintype "input"))
      (node (ref "U0") (pin "3") (pinfunction "(SDA)_GPIO2_3") (pintype "unspecified"))
      (node (ref "U18") (pin "1") (pinfunction "IN+_1") (pintype "unspecified"))
      (node (ref "U18") (pin "3") (pinfunction "GND_3") (pintype "unspecified"))
      (node (ref "U19") (pin "3") (pinfunction "GND_3") (pintype "unspecified"))
      (node (ref "U20") (pin "3") (pinfunction "GND_3") (pintype "unspecified"))
      (node (ref "U21") (pin "3") (pinfunction "GND_3") (pintype "unspecified"))
      (node (ref "U22") (pin "2") (pinfunction "IN-_2") (pintype "unspecified"))
      (node (ref "U22") (pin "3") (pinfunction "GND_3") (pintype "unspecified"))
    )
    (net (code "72") (name "TXD") (class "Default")
      (node (ref "H1") (pin "2") (pinfunction "2_2") (pintype "input"))
      (node (ref "U0") (pin "8") (pinfunction "(TXD)_GPIO14_8") (pintype "unspecified"))
    )
    (net (code "73") (name "VS") (class "Default")
      (node (ref "CN6") (pin "2") (pinfunction "2_2") (pintype "input"))
      (node (ref "Q14") (pin "1") (pinfunction "S_1") (pintype "input"))
      (node (ref "Q14") (pin "2") (pinfunction "S_2") (pintype "input"))
      (node (ref "Q14") (pin "3") (pinfunction "S_3") (pintype "input"))
      (node (ref "R50") (pin "2") (pinfunction "2_2") (pintype "input"))
    )
    (net (code "74") (name "unconnected-(1W1-Pad2)") (class "Default")
      (node (ref "1W1") (pin "2") (pinfunction "2_2") (pintype "input+no_connect"))
    )
    (net (code "75") (name "unconnected-(1W1-Pad6)") (class "Default")
      (node (ref "1W1") (pin "6") (pinfunction "6_6") (pintype "input+no_connect"))
    )
    (net (code "76") (name "unconnected-(1W2-Pad2)") (class "Default")
      (node (ref "1W2") (pin "2") (pinfunction "2_2") (pintype "input+no_connect"))
    )
    (net (code "77") (name "unconnected-(1W2-Pad6)") (class "Default")
      (node (ref "1W2") (pin "6") (pinfunction "6_6") (pintype "input+no_connect"))
    )
    (net (code "78") (name "unconnected-(CN6-Pad3)") (class "Default")
      (node (ref "CN6") (pin "3") (pinfunction "3_3") (pintype "input+no_connect"))
    )
    (net (code "79") (name "unconnected-(D5-A-Pad1)") (class "Default")
      (node (ref "D5") (pin "1") (pinfunction "A_1") (pintype "input+no_connect"))
    )
    (net (code "80") (name "unconnected-(D5-AC-Pad6)") (class "Default")
      (node (ref "D5") (pin "6") (pinfunction "AC_6") (pintype "input+no_connect"))
    )
    (net (code "81") (name "unconnected-(D5-C-Pad2)") (class "Default")
      (node (ref "D5") (pin "2") (pinfunction "C_2") (pintype "input+no_connect"))
    )
    (net (code "82") (name "unconnected-(DC0-Pad3)") (class "Default")
      (node (ref "DC0") (pin "3") (pinfunction "3_3") (pintype "input+no_connect"))
    )
    (net (code "83") (name "unconnected-(DC0-Pad4)") (class "Default")
      (node (ref "DC0") (pin "4") (pinfunction "4_4") (pintype "input+no_connect"))
    )
    (net (code "84") (name "unconnected-(U0-(CE0)_GPIO8-Pad24)") (class "Default")
      (node (ref "U0") (pin "24") (pinfunction "(CE0)_GPIO8_24") (pintype "unspecified+no_connect"))
    )
    (net (code "85") (name "unconnected-(U0-(CE1)_GPIO7-Pad26)") (class "Default")
      (node (ref "U0") (pin "26") (pinfunction "(CE1)_GPIO7_26") (pintype "unspecified+no_connect"))
    )
    (net (code "86") (name "unconnected-(U0-(MISO)_GPIO9-Pad21)") (class "Default")
      (node (ref "U0") (pin "21") (pinfunction "(MISO)_GPIO9_21") (pintype "unspecified+no_connect"))
    )
    (net (code "87") (name "unconnected-(U0-(MISO)_GPIO19-Pad35)") (class "Default")
      (node (ref "U0") (pin "35") (pinfunction "(MISO)_GPIO19_35") (pintype "unspecified+no_connect"))
    )
    (net (code "88") (name "unconnected-(U0-(MOSI)_GPIO10-Pad19)") (class "Default")
      (node (ref "U0") (pin "19") (pinfunction "(MOSI)_GPIO10_19") (pintype "unspecified+no_connect"))
    )
    (net (code "89") (name "unconnected-(U0-(PWM0)_GPIO12-Pad32)") (class "Default")
      (node (ref "U0") (pin "32") (pinfunction "(PWM0)_GPIO12_32") (pintype "unspecified+no_connect"))
    )
    (net (code "90") (name "unconnected-(U0-(SCLK)_GPIO11-Pad23)") (class "Default")
      (node (ref "U0") (pin "23") (pinfunction "(SCLK)_GPIO11_23") (pintype "unspecified+no_connect"))
    )
    (net (code "91") (name "unconnected-(U0-GPIO5-Pad29)") (class "Default")
      (node (ref "U0") (pin "29") (pinfunction "GPIO5_29") (pintype "unspecified+no_connect"))
    )
    (net (code "92") (name "unconnected-(U0-GPIO6-Pad31)") (class "Default")
      (node (ref "U0") (pin "31") (pinfunction "GPIO6_31") (pintype "unspecified+no_connect"))
    )
    (net (code "93") (name "unconnected-(U0-GPIO16-Pad36)") (class "Default")
      (node (ref "U0") (pin "36") (pinfunction "GPIO16_36") (pintype "unspecified+no_connect"))
    )
    (net (code "94") (name "unconnected-(U0-GPIO17-Pad11)") (class "Default")
      (node (ref "U0") (pin "11") (pinfunction "GPIO17_11") (pintype "unspecified+no_connect"))
    )
    (net (code "95") (name "unconnected-(U0-GPIO22-Pad15)") (class "Default")
      (node (ref "U0") (pin "15") (pinfunction "GPIO22_15") (pintype "unspecified+no_connect"))
    )
    (net (code "96") (name "unconnected-(U0-GPIO23-Pad16)") (class "Default")
      (node (ref "U0") (pin "16") (pinfunction "GPIO23_16") (pintype "unspecified+no_connect"))
    )
    (net (code "97") (name "unconnected-(U0-GPIO24-Pad18)") (class "Default")
      (node (ref "U0") (pin "18") (pinfunction "GPIO24_18") (pintype "unspecified+no_connect"))
    )
    (net (code "98") (name "unconnected-(U0-GPIO27-Pad13)") (class "Default")
      (node (ref "U0") (pin "13") (pinfunction "GPIO27_13") (pintype "unspecified+no_connect"))
    )
    (net (code "99") (name "unconnected-(U23-A0-Pad1)") (class "Default")
      (node (ref "U23") (pin "1") (pinfunction "A0_1") (pintype "input+no_connect"))
    )
    (net (code "100") (name "unconnected-(U23-A1-Pad2)") (class "Default")
      (node (ref "U23") (pin "2") (pinfunction "A1_2") (pintype "input+no_connect"))
    )
  )
)
